# KK_Triangle_cubic.net
KiCad netlist of a schematic drawn in Altium Designer
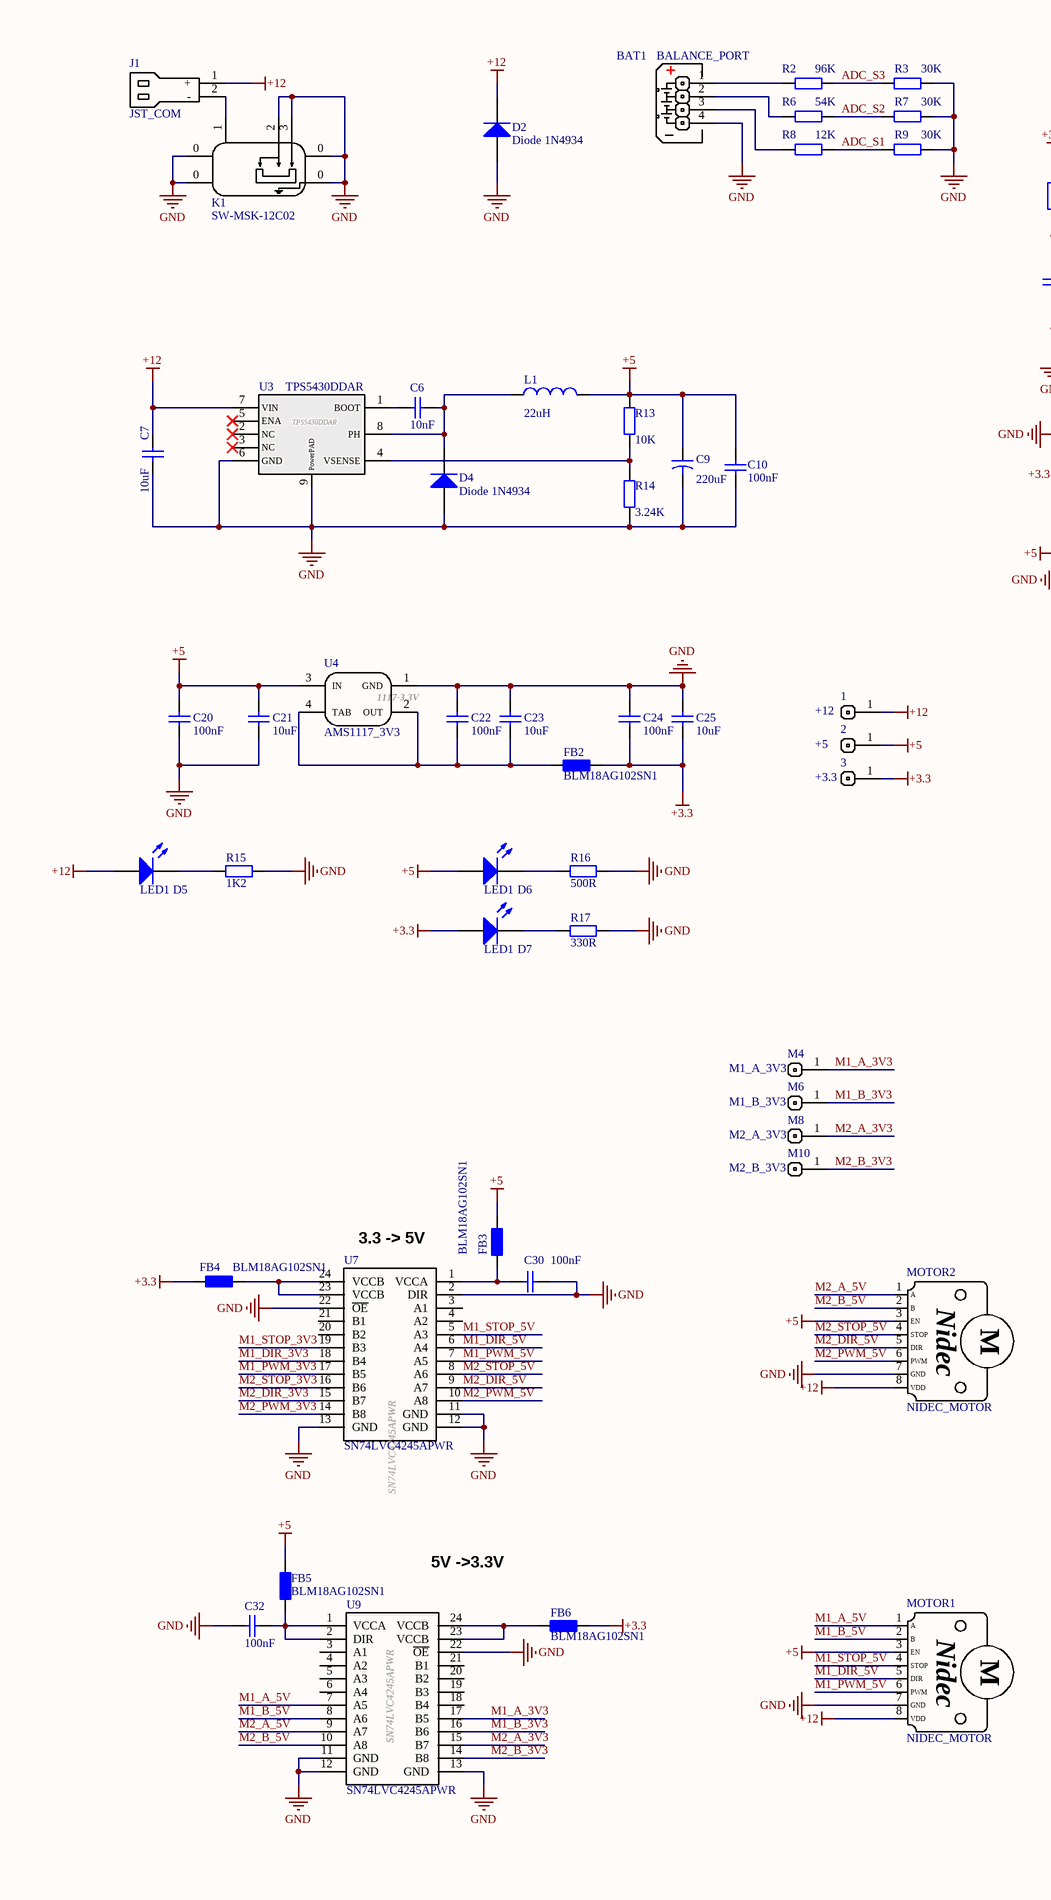
[diagram p0: KK_Triangle_cubic.SchDoc, left]
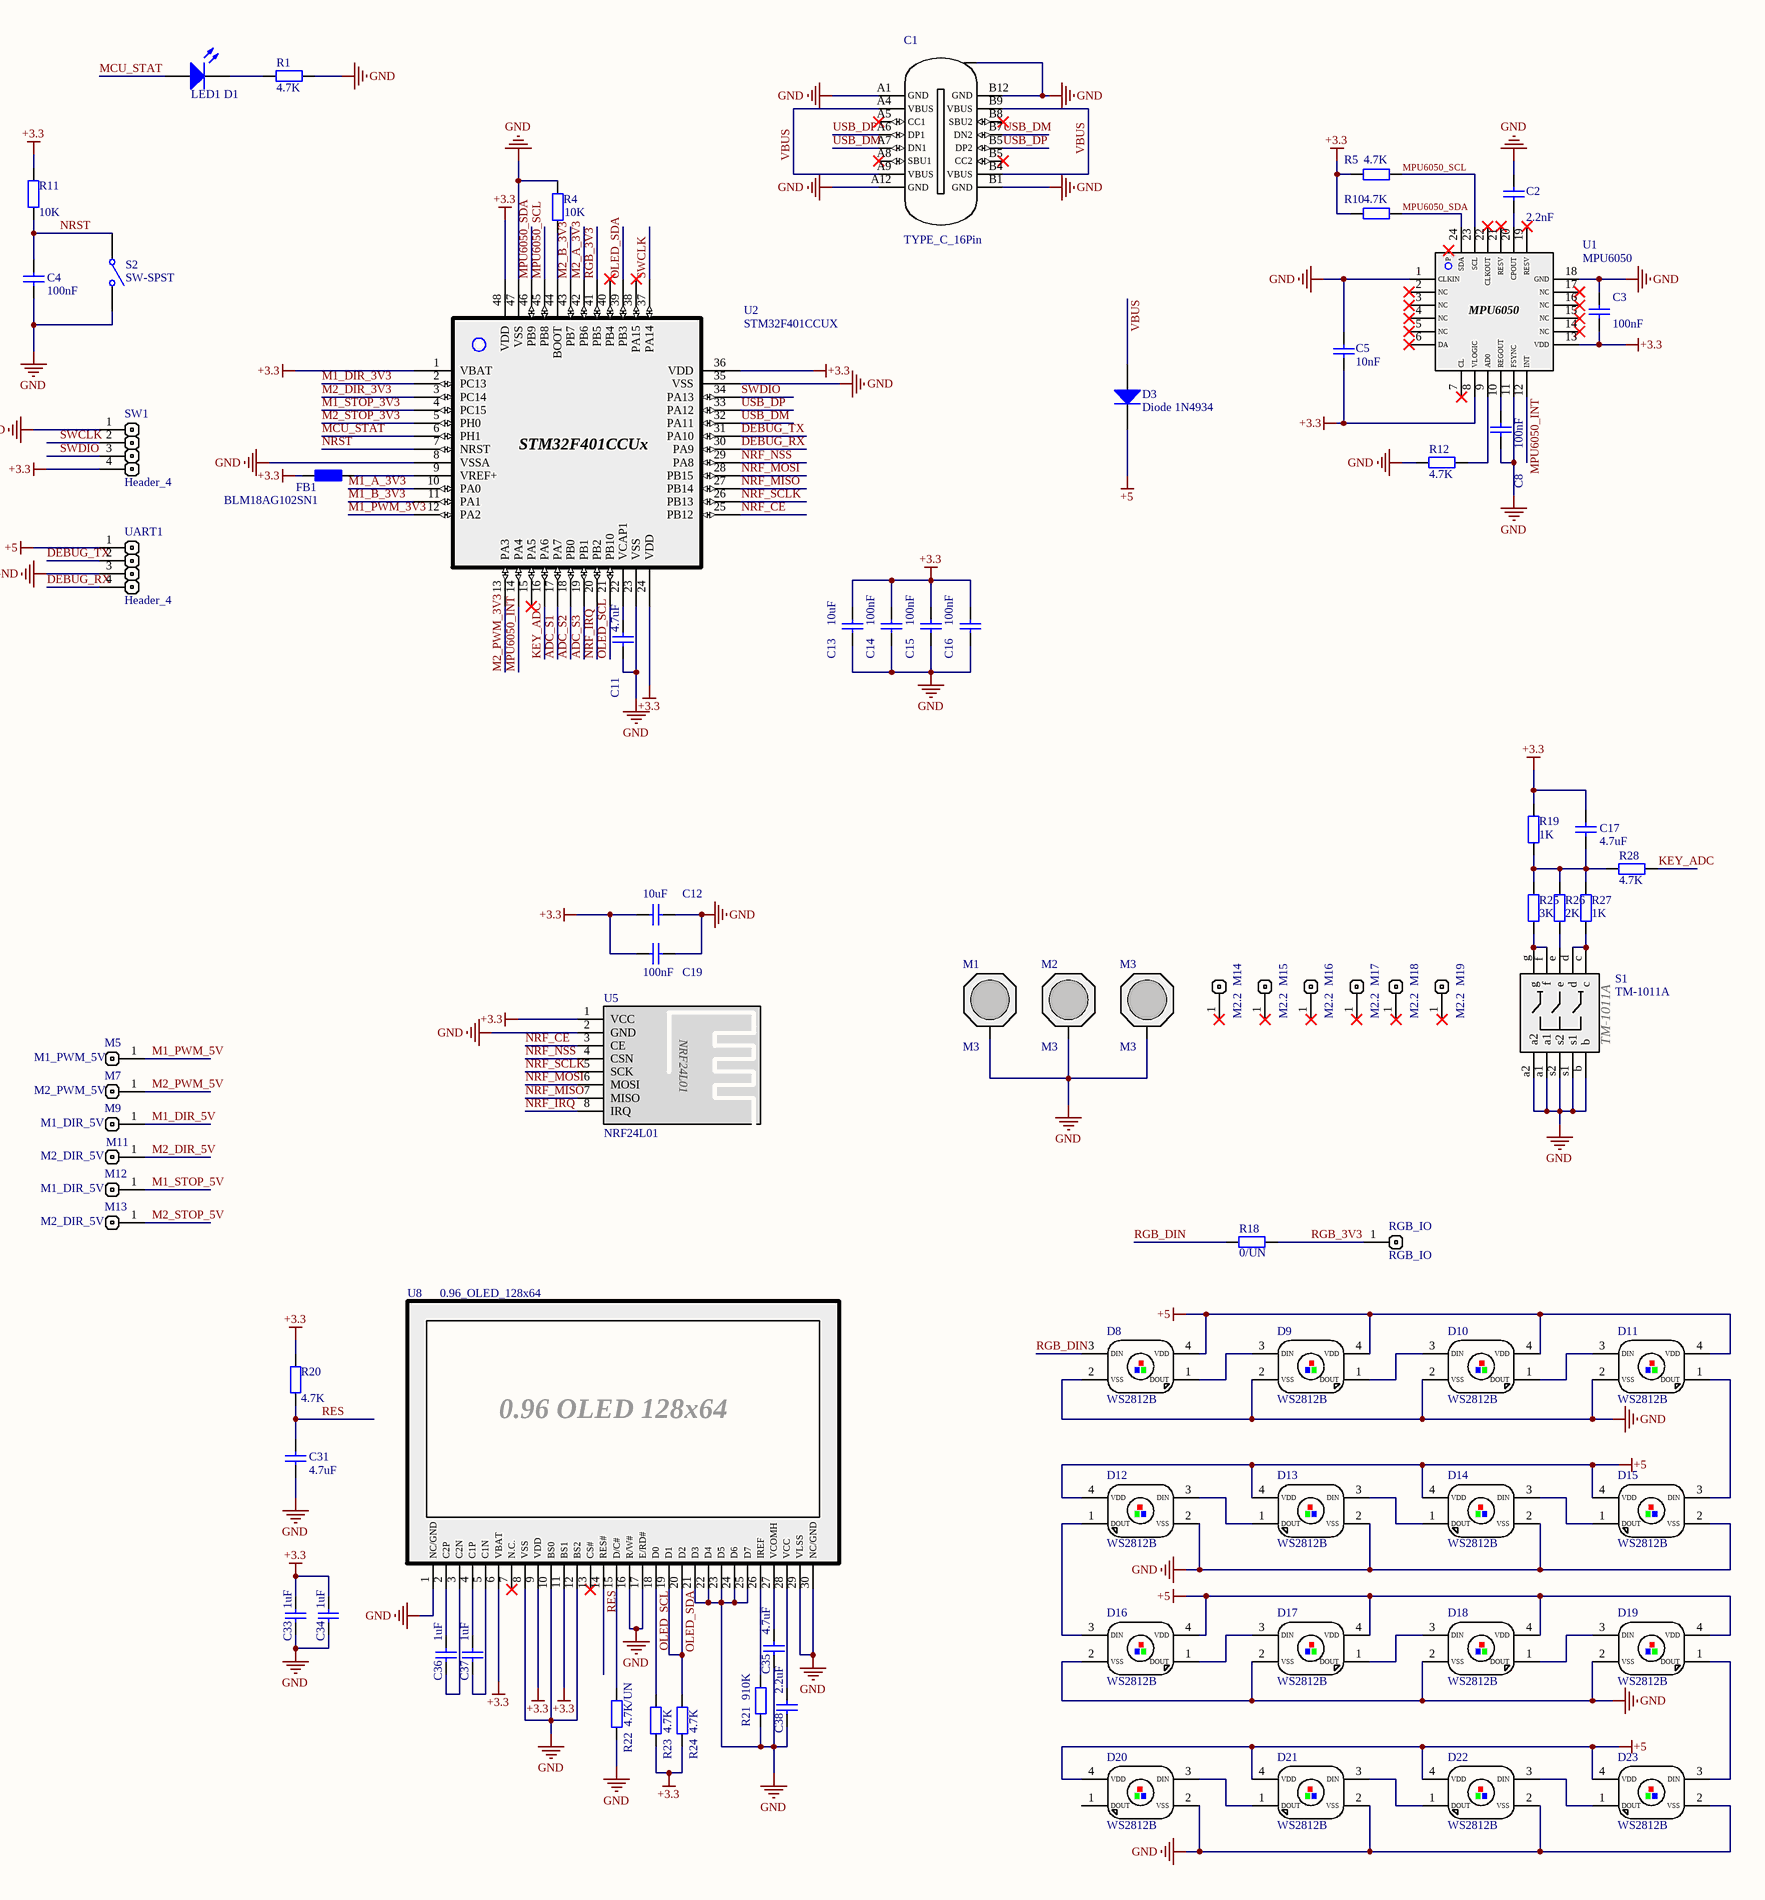
[diagram p1: KK_Triangle_cubic.SchDoc, right]

(export (version "E")
  (design (tool "Eeschema 10.0.6"))
  (components
    (comp (ref "1")
      (value "+12")
      (footprint "TEST_POINT")
      (libsource (lib "KK_Triangle_cubic") (part "TEST_POINT"))
    )
    (comp (ref "2")
      (value "+5")
      (footprint "TEST_POINT")
      (libsource (lib "KK_Triangle_cubic") (part "TEST_POINT"))
    )
    (comp (ref "3")
      (value "+3.3")
      (footprint "TEST_POINT")
      (libsource (lib "KK_Triangle_cubic") (part "TEST_POINT"))
    )
    (comp (ref "BAT1")
      (value "BALANCE_PORT")
      (footprint "XH2.54-LI-4P")
      (libsource (lib "KK_Triangle_cubic") (part "BALANCE_PORT"))
    )
    (comp (ref "C1")
      (value "TYPE_C_16Pin")
      (footprint "USB-C-SMD_TYPE-C-USB-5")
      (libsource (lib "KK_Analog") (part "TYPE_C_16Pin"))
    )
    (comp (ref "C2")
      (value "2.2nF")
      (footprint "C 0603_M")
      (description "Capacitor")
      (fields (field (name "Comment") "Cap") (field (name "PUBLISHER") "Altium Limited"))
      (libsource (lib "Miscellaneous Devices") (part "Cap"))
    )
    (comp (ref "C3")
      (value "100nF")
      (footprint "C 0603_M")
      (description "Capacitor")
      (fields (field (name "Comment") "Cap") (field (name "PUBLISHER") "Altium Limited"))
      (libsource (lib "Miscellaneous Devices") (part "Cap"))
    )
    (comp (ref "C4")
      (value "100nF")
      (footprint "C 0603_M")
      (description "Capacitor")
      (fields (field (name "Comment") "Cap") (field (name "PUBLISHER") "Altium Limited"))
      (libsource (lib "Miscellaneous Devices") (part "Cap"))
    )
    (comp (ref "C5")
      (value "10nF")
      (footprint "C 0603_M")
      (description "Capacitor")
      (fields (field (name "Comment") "Cap") (field (name "PUBLISHER") "Altium Limited"))
      (libsource (lib "Miscellaneous Devices") (part "Cap"))
    )
    (comp (ref "C6")
      (value "10nF")
      (footprint "C 0603_M")
      (description "Capacitor")
      (fields (field (name "Comment") "Cap") (field (name "PUBLISHER") "Altium Limited"))
      (libsource (lib "Miscellaneous Devices") (part "Cap"))
    )
    (comp (ref "C7")
      (value "10uF")
      (footprint "C 0603_M")
      (description "Capacitor")
      (fields (field (name "Comment") "Cap") (field (name "PUBLISHER") "Altium Limited"))
      (libsource (lib "Miscellaneous Devices") (part "Cap"))
    )
    (comp (ref "C8")
      (value "100nF")
      (footprint "C 0603_M")
      (description "Capacitor")
      (fields (field (name "Comment") "Cap") (field (name "PUBLISHER") "Altium Limited"))
      (libsource (lib "Miscellaneous Devices") (part "Cap"))
    )
    (comp (ref "C9")
      (value "220uF")
      (footprint "CM D(6.3*7.7)")
      (description "Capacitor")
      (fields (field (name "Comment") "Cap2") (field (name "PUBLISHER") "Altium Limited"))
      (libsource (lib "Miscellaneous Devices") (part "Cap2"))
    )
    (comp (ref "C10")
      (value "100nF")
      (footprint "C 0603_M")
      (description "Capacitor")
      (fields (field (name "Comment") "Cap") (field (name "PUBLISHER") "Altium Limited"))
      (libsource (lib "Miscellaneous Devices") (part "Cap"))
    )
    (comp (ref "C11")
      (value "4.7uF")
      (footprint "C 0603_M")
      (description "Capacitor")
      (fields (field (name "Comment") "Cap") (field (name "PUBLISHER") "Altium Limited"))
      (libsource (lib "Miscellaneous Devices") (part "Cap"))
    )
    (comp (ref "C12")
      (value "10uF")
      (footprint "C 0603_M")
      (description "Capacitor")
      (fields (field (name "Comment") "Cap") (field (name "PUBLISHER") "Altium Limited"))
      (libsource (lib "Miscellaneous Devices") (part "Cap"))
    )
    (comp (ref "C13")
      (value "10uF")
      (footprint "C 0603_M")
      (description "Capacitor")
      (fields (field (name "Comment") "Cap") (field (name "PUBLISHER") "Altium Limited"))
      (libsource (lib "Miscellaneous Devices") (part "Cap"))
    )
    (comp (ref "C14")
      (value "100nF")
      (footprint "C 0603_M")
      (description "Capacitor")
      (fields (field (name "Comment") "Cap") (field (name "PUBLISHER") "Altium Limited"))
      (libsource (lib "Miscellaneous Devices") (part "Cap"))
    )
    (comp (ref "C15")
      (value "100nF")
      (footprint "C 0603_M")
      (description "Capacitor")
      (fields (field (name "Comment") "Cap") (field (name "PUBLISHER") "Altium Limited"))
      (libsource (lib "Miscellaneous Devices") (part "Cap"))
    )
    (comp (ref "C16")
      (value "100nF")
      (footprint "C 0603_M")
      (description "Capacitor")
      (fields (field (name "Comment") "Cap") (field (name "PUBLISHER") "Altium Limited"))
      (libsource (lib "Miscellaneous Devices") (part "Cap"))
    )
    (comp (ref "C17")
      (value "4.7uF")
      (footprint "C 0603_M")
      (description "Capacitor")
      (fields (field (name "Comment") "Cap") (field (name "PUBLISHER") "Altium Limited"))
      (libsource (lib "Miscellaneous Devices") (part "Cap"))
    )
    (comp (ref "C19")
      (value "100nF")
      (footprint "C 0603_M")
      (description "Capacitor")
      (fields (field (name "Comment") "Cap") (field (name "PUBLISHER") "Altium Limited"))
      (libsource (lib "Miscellaneous Devices") (part "Cap"))
    )
    (comp (ref "C20")
      (value "100nF")
      (footprint "C 0603_M")
      (description "Capacitor")
      (fields (field (name "Comment") "Cap") (field (name "PUBLISHER") "Altium Limited"))
      (libsource (lib "Miscellaneous Devices") (part "Cap"))
    )
    (comp (ref "C21")
      (value "10uF")
      (footprint "C 0603_M")
      (description "Capacitor")
      (fields (field (name "Comment") "Cap") (field (name "PUBLISHER") "Altium Limited"))
      (libsource (lib "Miscellaneous Devices") (part "Cap"))
    )
    (comp (ref "C22")
      (value "100nF")
      (footprint "C 0603_M")
      (description "Capacitor")
      (fields (field (name "Comment") "Cap") (field (name "PUBLISHER") "Altium Limited"))
      (libsource (lib "Miscellaneous Devices") (part "Cap"))
    )
    (comp (ref "C23")
      (value "10uF")
      (footprint "C 0603_M")
      (description "Capacitor")
      (fields (field (name "Comment") "Cap") (field (name "PUBLISHER") "Altium Limited"))
      (libsource (lib "Miscellaneous Devices") (part "Cap"))
    )
    (comp (ref "C24")
      (value "100nF")
      (footprint "C 0603_M")
      (description "Capacitor")
      (fields (field (name "Comment") "Cap") (field (name "PUBLISHER") "Altium Limited"))
      (libsource (lib "Miscellaneous Devices") (part "Cap"))
    )
    (comp (ref "C25")
      (value "10uF")
      (footprint "C 0603_M")
      (description "Capacitor")
      (fields (field (name "Comment") "Cap") (field (name "PUBLISHER") "Altium Limited"))
      (libsource (lib "Miscellaneous Devices") (part "Cap"))
    )
    (comp (ref "C30")
      (value "100nF")
      (footprint "C 0603_M")
      (description "Capacitor")
      (fields (field (name "Comment") "Cap") (field (name "PUBLISHER") "Altium Limited"))
      (libsource (lib "Miscellaneous Devices") (part "Cap"))
    )
    (comp (ref "C31")
      (value "4.7uF")
      (footprint "C 0603_M")
      (description "Capacitor")
      (fields (field (name "Comment") "Cap") (field (name "PUBLISHER") "Altium Limited"))
      (libsource (lib "Miscellaneous Devices") (part "Cap"))
    )
    (comp (ref "C32")
      (value "100nF")
      (footprint "C 0603_M")
      (description "Capacitor")
      (fields (field (name "Comment") "Cap") (field (name "PUBLISHER") "Altium Limited"))
      (libsource (lib "Miscellaneous Devices") (part "Cap"))
    )
    (comp (ref "C33")
      (value "1uF")
      (footprint "C 0603_M")
      (description "Capacitor")
      (fields (field (name "Comment") "Cap") (field (name "PUBLISHER") "Altium Limited"))
      (libsource (lib "Miscellaneous Devices") (part "Cap"))
    )
    (comp (ref "C34")
      (value "1uF")
      (footprint "C 0603_M")
      (description "Capacitor")
      (fields (field (name "Comment") "Cap") (field (name "PUBLISHER") "Altium Limited"))
      (libsource (lib "Miscellaneous Devices") (part "Cap"))
    )
    (comp (ref "C35")
      (value "4.7uF")
      (footprint "C 0603_M")
      (description "Capacitor")
      (fields (field (name "Comment") "Cap") (field (name "PUBLISHER") "Altium Limited"))
      (libsource (lib "Miscellaneous Devices") (part "Cap"))
    )
    (comp (ref "C36")
      (value "1uF")
      (footprint "C 0603_M")
      (description "Capacitor")
      (fields (field (name "Comment") "Cap") (field (name "PUBLISHER") "Altium Limited"))
      (libsource (lib "Miscellaneous Devices") (part "Cap"))
    )
    (comp (ref "C37")
      (value "1uF")
      (footprint "C 0603_M")
      (description "Capacitor")
      (fields (field (name "Comment") "Cap") (field (name "PUBLISHER") "Altium Limited"))
      (libsource (lib "Miscellaneous Devices") (part "Cap"))
    )
    (comp (ref "C38")
      (value "2.2uF")
      (footprint "C 0603_M")
      (description "Capacitor")
      (fields (field (name "Comment") "Cap") (field (name "PUBLISHER") "Altium Limited"))
      (libsource (lib "Miscellaneous Devices") (part "Cap"))
    )
    (comp (ref "D1")
      (value "LED1")
      (footprint "LED 0805G")
      (description "Typical RED GaAs LED")
      (fields (field (name "PUBLISHER") "Altium Limited"))
      (libsource (lib "Miscellaneous Devices") (part "LED1"))
    )
    (comp (ref "D2")
      (value "Diode 1N4934")
      (footprint "1N5819(SMD)")
      (description "1 Amp Fast Recovery Rectifier")
      (fields (field (name "PUBLISHER") "Altium Limited"))
      (libsource (lib "Miscellaneous Devices") (part "Diode 1N4934"))
    )
    (comp (ref "D3")
      (value "Diode 1N4934")
      (footprint "SOD-323")
      (description "1 Amp Fast Recovery Rectifier")
      (fields (field (name "PUBLISHER") "Altium Limited"))
      (libsource (lib "Miscellaneous Devices") (part "Diode 1N4934"))
    )
    (comp (ref "D4")
      (value "Diode 1N4934")
      (footprint "1N5819(SMD)")
      (description "1 Amp Fast Recovery Rectifier")
      (fields (field (name "PUBLISHER") "Altium Limited"))
      (libsource (lib "Miscellaneous Devices") (part "Diode 1N4934"))
    )
    (comp (ref "D5")
      (value "LED1")
      (footprint "LED 0805G")
      (description "Typical RED GaAs LED")
      (fields (field (name "PUBLISHER") "Altium Limited"))
      (libsource (lib "Miscellaneous Devices") (part "LED1"))
    )
    (comp (ref "D6")
      (value "LED1")
      (footprint "LED 0805G")
      (description "Typical RED GaAs LED")
      (fields (field (name "PUBLISHER") "Altium Limited"))
      (libsource (lib "Miscellaneous Devices") (part "LED1"))
    )
    (comp (ref "D7")
      (value "LED1")
      (footprint "LED 0805G")
      (description "Typical RED GaAs LED")
      (fields (field (name "PUBLISHER") "Altium Limited"))
      (libsource (lib "Miscellaneous Devices") (part "LED1"))
    )
    (comp (ref "D8")
      (value "WS2812B")
      (footprint "WS2812B-2020")
      (libsource (lib "") (part "WS2812B_2020_1"))
    )
    (comp (ref "D9")
      (value "WS2812B")
      (footprint "WS2812B-2020")
      (libsource (lib "") (part "WS2812B_2020_1"))
    )
    (comp (ref "D10")
      (value "WS2812B")
      (footprint "WS2812B-2020")
      (libsource (lib "") (part "WS2812B_2020_1"))
    )
    (comp (ref "D11")
      (value "WS2812B")
      (footprint "WS2812B-2020")
      (libsource (lib "") (part "WS2812B_2020_1"))
    )
    (comp (ref "D12")
      (value "WS2812B")
      (footprint "WS2812B-2020")
      (libsource (lib "KK_Triangle_cubic") (part "WS2812B_2020"))
    )
    (comp (ref "D13")
      (value "WS2812B")
      (footprint "WS2812B-2020")
      (libsource (lib "KK_Triangle_cubic") (part "WS2812B_2020"))
    )
    (comp (ref "D14")
      (value "WS2812B")
      (footprint "WS2812B-2020")
      (libsource (lib "KK_Triangle_cubic") (part "WS2812B_2020"))
    )
    (comp (ref "D15")
      (value "WS2812B")
      (footprint "WS2812B-2020")
      (libsource (lib "KK_Triangle_cubic") (part "WS2812B_2020"))
    )
    (comp (ref "D16")
      (value "WS2812B")
      (footprint "WS2812B-2020")
      (libsource (lib "") (part "WS2812B_2020_1"))
    )
    (comp (ref "D17")
      (value "WS2812B")
      (footprint "WS2812B-2020")
      (libsource (lib "") (part "WS2812B_2020_1"))
    )
    (comp (ref "D18")
      (value "WS2812B")
      (footprint "WS2812B-2020")
      (libsource (lib "") (part "WS2812B_2020_1"))
    )
    (comp (ref "D19")
      (value "WS2812B")
      (footprint "WS2812B-2020")
      (libsource (lib "") (part "WS2812B_2020_1"))
    )
    (comp (ref "D20")
      (value "WS2812B")
      (footprint "WS2812B-2020")
      (libsource (lib "KK_Triangle_cubic") (part "WS2812B_2020"))
    )
    (comp (ref "D21")
      (value "WS2812B")
      (footprint "WS2812B-2020")
      (libsource (lib "KK_Triangle_cubic") (part "WS2812B_2020"))
    )
    (comp (ref "D22")
      (value "WS2812B")
      (footprint "WS2812B-2020")
      (libsource (lib "KK_Triangle_cubic") (part "WS2812B_2020"))
    )
    (comp (ref "D23")
      (value "WS2812B")
      (footprint "WS2812B-2020")
      (libsource (lib "KK_Triangle_cubic") (part "WS2812B_2020"))
    )
    (comp (ref "FB1")
      (value "BLM18AG102SN1")
      (footprint "L 0603")
      (libsource (lib "") (part "BLM18AG102SN1_2"))
    )
    (comp (ref "FB2")
      (value "BLM18AG102SN1")
      (footprint "L 0603")
      (libsource (lib "") (part "BLM18AG102SN1_2"))
    )
    (comp (ref "FB3")
      (value "BLM18AG102SN1")
      (footprint "L 0603")
      (libsource (lib "KK_Triangle_cubic") (part "BLM18AG102SN1"))
    )
    (comp (ref "FB4")
      (value "BLM18AG102SN1")
      (footprint "L 0603")
      (libsource (lib "") (part "BLM18AG102SN1_1"))
    )
    (comp (ref "FB5")
      (value "BLM18AG102SN1")
      (footprint "L 0603")
      (libsource (lib "") (part "BLM18AG102SN1_2"))
    )
    (comp (ref "FB6")
      (value "BLM18AG102SN1")
      (footprint "L 0603")
      (libsource (lib "KK_Triangle_cubic") (part "BLM18AG102SN1"))
    )
    (comp (ref "J1")
      (value "JST_COM")
      (footprint "JST_COM")
      (libsource (lib "KK_Triangle_cubic") (part "JST_COM"))
    )
    (comp (ref "K1")
      (value "SW-MSK-12C02")
      (footprint "MSK-12C01-07")
      (libsource (lib "KK_Triangle_cubic") (part "SW-MSK-12C02"))
    )
    (comp (ref "L1")
      (value "22uH")
      (footprint "CDRH74")
      (description "Inductor")
      (fields (field (name "PUBLISHER") "Altium Limited"))
      (libsource (lib "Miscellaneous Devices") (part "Inductor"))
    )
    (comp (ref "M1") (value "M3") (footprint "M3x40+6_L") (libsource (lib "KK_Triangle_cubic") (part "M3")))
    (comp (ref "M2") (value "M3") (footprint "M3x40+6_L") (libsource (lib "KK_Triangle_cubic") (part "M3")))
    (comp (ref "M3") (value "M3") (footprint "M3x40+6_L") (libsource (lib "KK_Triangle_cubic") (part "M3")))
    (comp (ref "M4")
      (value "M1_A_3V3")
      (footprint "TEST_POINT")
      (libsource (lib "KK_Triangle_cubic") (part "TEST_POINT"))
    )
    (comp (ref "M5")
      (value "M1_PWM_5V")
      (footprint "TEST_POINT")
      (libsource (lib "KK_Triangle_cubic") (part "TEST_POINT"))
    )
    (comp (ref "M6")
      (value "M1_B_3V3")
      (footprint "TEST_POINT")
      (libsource (lib "KK_Triangle_cubic") (part "TEST_POINT"))
    )
    (comp (ref "M7")
      (value "M2_PWM_5V")
      (footprint "TEST_POINT")
      (libsource (lib "KK_Triangle_cubic") (part "TEST_POINT"))
    )
    (comp (ref "M8")
      (value "M2_A_3V3")
      (footprint "TEST_POINT")
      (libsource (lib "KK_Triangle_cubic") (part "TEST_POINT"))
    )
    (comp (ref "M9")
      (value "M1_DIR_5V")
      (footprint "TEST_POINT")
      (libsource (lib "KK_Triangle_cubic") (part "TEST_POINT"))
    )
    (comp (ref "M10")
      (value "M2_B_3V3")
      (footprint "TEST_POINT")
      (libsource (lib "KK_Triangle_cubic") (part "TEST_POINT"))
    )
    (comp (ref "M11")
      (value "M2_DIR_5V")
      (footprint "TEST_POINT")
      (libsource (lib "KK_Triangle_cubic") (part "TEST_POINT"))
    )
    (comp (ref "M12")
      (value "M1_DIR_5V")
      (footprint "TEST_POINT")
      (libsource (lib "KK_Triangle_cubic") (part "TEST_POINT"))
    )
    (comp (ref "M13")
      (value "M2_DIR_5V")
      (footprint "TEST_POINT")
      (libsource (lib "KK_Triangle_cubic") (part "TEST_POINT"))
    )
    (comp (ref "M14") (value "M2.2") (footprint "H2.2") (libsource (lib "KK_Triangle_cubic") (part "M2.2")))
    (comp (ref "M15") (value "M2.2") (footprint "H2.2") (libsource (lib "KK_Triangle_cubic") (part "M2.2")))
    (comp (ref "M16") (value "M2.2") (footprint "H2.2") (libsource (lib "KK_Triangle_cubic") (part "M2.2")))
    (comp (ref "M17") (value "M2.2") (footprint "H2.2") (libsource (lib "KK_Triangle_cubic") (part "M2.2")))
    (comp (ref "M18") (value "M2.2") (footprint "H2.2") (libsource (lib "KK_Triangle_cubic") (part "M2.2")))
    (comp (ref "M19") (value "M2.2") (footprint "H2.2") (libsource (lib "KK_Triangle_cubic") (part "M2.2")))
    (comp (ref "MOTOR1")
      (value "NIDEC_MOTOR")
      (footprint "MX 1.25-LS-8P")
      (libsource (lib "KK_Triangle_cubic") (part "NIDEC_MOTOR"))
    )
    (comp (ref "MOTOR2")
      (value "NIDEC_MOTOR")
      (footprint "MX 1.25-LS-8P")
      (libsource (lib "KK_Triangle_cubic") (part "NIDEC_MOTOR"))
    )
    (comp (ref "R1")
      (value "4.7K")
      (footprint "R 0603_M")
      (description "Resistor")
      (fields (field (name "Comment") "Res2") (field (name "PUBLISHER") "Altium Limited"))
      (libsource (lib "Miscellaneous Devices") (part "Res2"))
    )
    (comp (ref "R2")
      (value "96K")
      (footprint "R 0603_M")
      (description "Resistor")
      (fields (field (name "Comment") "Res2") (field (name "PUBLISHER") "Altium Limited"))
      (libsource (lib "Miscellaneous Devices") (part "Res2"))
    )
    (comp (ref "R3")
      (value "30K")
      (footprint "R 0603_M")
      (description "Resistor")
      (fields (field (name "Comment") "Res2") (field (name "PUBLISHER") "Altium Limited"))
      (libsource (lib "Miscellaneous Devices") (part "Res2"))
    )
    (comp (ref "R4")
      (value "10K")
      (footprint "R 0603_M")
      (description "Resistor")
      (fields (field (name "Comment") "Res2") (field (name "PUBLISHER") "Altium Limited"))
      (libsource (lib "") (part "Res2_2"))
    )
    (comp (ref "R5")
      (value "4.7K")
      (footprint "R 0603_M")
      (description "Resistor")
      (fields (field (name "Comment") "Res2") (field (name "PUBLISHER") "Altium Limited"))
      (libsource (lib "Miscellaneous Devices") (part "Res2"))
    )
    (comp (ref "R6")
      (value "54K")
      (footprint "R 0603_M")
      (description "Resistor")
      (fields (field (name "Comment") "Res2") (field (name "PUBLISHER") "Altium Limited"))
      (libsource (lib "Miscellaneous Devices") (part "Res2"))
    )
    (comp (ref "R7")
      (value "30K")
      (footprint "R 0603_M")
      (description "Resistor")
      (fields (field (name "Comment") "Res2") (field (name "PUBLISHER") "Altium Limited"))
      (libsource (lib "Miscellaneous Devices") (part "Res2"))
    )
    (comp (ref "R8")
      (value "12K")
      (footprint "R 0603_M")
      (description "Resistor")
      (fields (field (name "Comment") "Res2") (field (name "PUBLISHER") "Altium Limited"))
      (libsource (lib "Miscellaneous Devices") (part "Res2"))
    )
    (comp (ref "R9")
      (value "30K")
      (footprint "R 0603_M")
      (description "Resistor")
      (fields (field (name "Comment") "Res2") (field (name "PUBLISHER") "Altium Limited"))
      (libsource (lib "Miscellaneous Devices") (part "Res2"))
    )
    (comp (ref "R10")
      (value "4.7K")
      (footprint "R 0603_M")
      (description "Resistor")
      (fields (field (name "Comment") "Res2") (field (name "PUBLISHER") "Altium Limited"))
      (libsource (lib "Miscellaneous Devices") (part "Res2"))
    )
    (comp (ref "R11")
      (value "10K")
      (footprint "R 0603_M")
      (description "Resistor")
      (fields (field (name "Comment") "Res2") (field (name "PUBLISHER") "Altium Limited"))
      (libsource (lib "") (part "Res2_2"))
    )
    (comp (ref "R12")
      (value "4.7K")
      (footprint "R 0603_M")
      (description "Resistor")
      (fields (field (name "Comment") "Res2") (field (name "PUBLISHER") "Altium Limited"))
      (libsource (lib "") (part "Res2_1"))
    )
    (comp (ref "R13")
      (value "10K")
      (footprint "R 0603_M")
      (description "Resistor")
      (fields (field (name "Comment") "Res2") (field (name "PUBLISHER") "Altium Limited"))
      (libsource (lib "") (part "Res2_2"))
    )
    (comp (ref "R14")
      (value "3.24K")
      (footprint "R 0603_M")
      (description "Resistor")
      (fields (field (name "Comment") "Res2") (field (name "PUBLISHER") "Altium Limited"))
      (libsource (lib "") (part "Res2_2"))
    )
    (comp (ref "R15")
      (value "1K2")
      (footprint "R 0603_M")
      (description "Resistor")
      (fields (field (name "Comment") "Res2") (field (name "PUBLISHER") "Altium Limited"))
      (libsource (lib "Miscellaneous Devices") (part "Res2"))
    )
    (comp (ref "R16")
      (value "500R")
      (footprint "R 0603_M")
      (description "Resistor")
      (fields (field (name "Comment") "Res2") (field (name "PUBLISHER") "Altium Limited"))
      (libsource (lib "Miscellaneous Devices") (part "Res2"))
    )
    (comp (ref "R17")
      (value "330R")
      (footprint "R 0603_M")
      (description "Resistor")
      (fields (field (name "Comment") "Res2") (field (name "PUBLISHER") "Altium Limited"))
      (libsource (lib "Miscellaneous Devices") (part "Res2"))
    )
    (comp (ref "R18")
      (value "0/UN")
      (footprint "R 0603_M")
      (description "Resistor")
      (fields (field (name "Comment") "Res2") (field (name "PUBLISHER") "Altium Limited"))
      (libsource (lib "") (part "Res2_1"))
    )
    (comp (ref "R19")
      (value "1K")
      (footprint "R 0603_M")
      (description "Resistor")
      (fields (field (name "Comment") "Res2") (field (name "PUBLISHER") "Altium Limited"))
      (libsource (lib "") (part "Res2_2"))
    )
    (comp (ref "R20")
      (value "4.7K")
      (footprint "R 0603_M")
      (description "Resistor")
      (fields (field (name "Comment") "Res2") (field (name "PUBLISHER") "Altium Limited"))
      (libsource (lib "") (part "Res2_2"))
    )
    (comp (ref "R21")
      (value "910K")
      (footprint "R 0603_M")
      (description "Resistor")
      (fields (field (name "Comment") "Res2") (field (name "PUBLISHER") "Altium Limited"))
      (libsource (lib "") (part "Res2_3"))
    )
    (comp (ref "R22")
      (value "4.7K/UN")
      (footprint "R 0603_M")
      (description "Resistor")
      (fields (field (name "Comment") "Res2") (field (name "PUBLISHER") "Altium Limited"))
      (libsource (lib "") (part "Res2_2"))
    )
    (comp (ref "R23")
      (value "4.7K")
      (footprint "R 0603_M")
      (description "Resistor")
      (fields (field (name "Comment") "Res2") (field (name "PUBLISHER") "Altium Limited"))
      (libsource (lib "") (part "Res2_2"))
    )
    (comp (ref "R24")
      (value "4.7K")
      (footprint "R 0603_M")
      (description "Resistor")
      (fields (field (name "Comment") "Res2") (field (name "PUBLISHER") "Altium Limited"))
      (libsource (lib "") (part "Res2_2"))
    )
    (comp (ref "R25")
      (value "3K")
      (footprint "R 0603_M")
      (description "Resistor")
      (fields (field (name "Comment") "Res2") (field (name "PUBLISHER") "Altium Limited"))
      (libsource (lib "") (part "Res2_3"))
    )
    (comp (ref "R26")
      (value "2K")
      (footprint "R 0603_M")
      (description "Resistor")
      (fields (field (name "Comment") "Res2") (field (name "PUBLISHER") "Altium Limited"))
      (libsource (lib "") (part "Res2_3"))
    )
    (comp (ref "R27")
      (value "1K")
      (footprint "R 0603_M")
      (description "Resistor")
      (fields (field (name "Comment") "Res2") (field (name "PUBLISHER") "Altium Limited"))
      (libsource (lib "") (part "Res2_3"))
    )
    (comp (ref "R28")
      (value "4.7K")
      (footprint "R 0603_M")
      (description "Resistor")
      (fields (field (name "Comment") "Res2") (field (name "PUBLISHER") "Altium Limited"))
      (libsource (lib "Miscellaneous Devices") (part "Res2"))
    )
    (comp (ref "RGB_IO")
      (value "RGB_IO")
      (footprint "TEST_POINT")
      (libsource (lib "KK_Triangle_cubic") (part "TEST_POINT"))
    )
    (comp (ref "S1")
      (value "TM-1011A")
      (footprint "TM-1011A")
      (libsource (lib "KK_Triangle_cubic") (part "TM-1011A"))
    )
    (comp (ref "S2")
      (value "SW-SPST")
      (footprint "TSW SMD-3*6*2.5")
      (description "Single-Pole, Single-Throw Switch")
      (fields (field (name "PUBLISHER") "Altium Limited"))
      (libsource (lib "Miscellaneous Devices") (part "SW-SPST"))
    )
    (comp (ref "SW1")
      (value "Header_4")
      (footprint "PH2.0-L-Z-4P")
      (libsource (lib "KK_Triangle_cubic") (part "Header_4"))
    )
    (comp (ref "U1")
      (value "MPU6050")
      (footprint "QFN24 4x4_M")
      (libsource (lib "KK_Triangle_cubic") (part "MPU6050"))
    )
    (comp (ref "U2")
      (value "STM32F401CCUX")
      (footprint "STM-UFQFPN48_M")
      (libsource (lib "KK_Triangle_cubic") (part "STM32F401CCUX"))
    )
    (comp (ref "U3")
      (value "TPS5430DDAR")
      (footprint "TPS5430DDAR")
      (libsource (lib "KK_Triangle_cubic") (part "TPS5430DDAR"))
    )
    (comp (ref "U4")
      (value "AMS1117_3V3")
      (footprint "SOT223_M")
      (libsource (lib "altium-import") (part "root_0_mirrored_AMS1117_3V3_"))
    )
    (comp (ref "U5")
      (value "NRF24L01")
      (footprint "NRF24L01_MIN")
      (libsource (lib "KK_Triangle_cubic") (part "NRF24L01"))
    )
    (comp (ref "U7")
      (value "SN74LVC4245APWR")
      (footprint "TSSOP24_M")
      (libsource (lib "") (part "SN74LVC4245APWR_1"))
    )
    (comp (ref "U8")
      (value "0.96_OLED_128x64")
      (footprint "0.96_OLED")
      (libsource (lib "KK_Triangle_cubic") (part "0.96_OLED_128x64"))
    )
    (comp (ref "U9")
      (value "SN74LVC4245APWR")
      (footprint "TSSOP24_M")
      (libsource (lib "KK_Triangle_cubic") (part "SN74LVC4245APWR"))
    )
    (comp (ref "UART1")
      (value "Header_4")
      (footprint "PH2.0-L-Z-4P")
      (libsource (lib "KK_Triangle_cubic") (part "Header_4"))
    )
  )
  (nets
    (net (code "1") (name "+3.3") (class "Default")
      (node (ref "3") (pin "1") (pinfunction "1_1") (pintype "power_in"))
      (node (ref "C12") (pin "2") (pinfunction "2_2") (pintype "passive"))
      (node (ref "C13") (pin "2") (pinfunction "2_2") (pintype "passive"))
      (node (ref "C14") (pin "2") (pinfunction "2_2") (pintype "passive"))
      (node (ref "C15") (pin "2") (pinfunction "2_2") (pintype "passive"))
      (node (ref "C16") (pin "2") (pinfunction "2_2") (pintype "passive"))
      (node (ref "C17") (pin "1") (pinfunction "1_1") (pintype "passive"))
      (node (ref "C19") (pin "2") (pinfunction "2_2") (pintype "passive"))
      (node (ref "C24") (pin "1") (pinfunction "1_1") (pintype "passive"))
      (node (ref "C25") (pin "1") (pinfunction "1_1") (pintype "passive"))
      (node (ref "C3") (pin "1") (pinfunction "1_1") (pintype "passive"))
      (node (ref "C33") (pin "2") (pinfunction "2_2") (pintype "passive"))
      (node (ref "C34") (pin "2") (pinfunction "2_2") (pintype "passive"))
      (node (ref "C5") (pin "1") (pinfunction "1_1") (pintype "passive"))
      (node (ref "D7") (pin "1") (pinfunction "A_1") (pintype "passive"))
      (node (ref "FB1") (pin "1") (pinfunction "1_1") (pintype "passive"))
      (node (ref "FB2") (pin "2") (pinfunction "2_2") (pintype "passive"))
      (node (ref "FB4") (pin "2") (pinfunction "2_2") (pintype "passive"))
      (node (ref "FB6") (pin "2") (pinfunction "2_2") (pintype "passive"))
      (node (ref "R10") (pin "2") (pinfunction "2_2") (pintype "passive"))
      (node (ref "R11") (pin "2") (pinfunction "2_2") (pintype "passive"))
      (node (ref "R19") (pin "2") (pinfunction "2_2") (pintype "passive"))
      (node (ref "R20") (pin "2") (pinfunction "2_2") (pintype "passive"))
      (node (ref "R23") (pin "1") (pinfunction "1_1") (pintype "passive"))
      (node (ref "R24") (pin "1") (pinfunction "1_1") (pintype "passive"))
      (node (ref "R5") (pin "2") (pinfunction "2_2") (pintype "passive"))
      (node (ref "SW1") (pin "4") (pinfunction "4_4") (pintype "power_in"))
      (node (ref "U1") (pin "13") (pinfunction "VDD_13") (pintype "power_in"))
      (node (ref "U1") (pin "8") (pinfunction "VLOGIC_8") (pintype "power_in"))
      (node (ref "U2") (pin "1") (pinfunction "VBAT_1") (pintype "power_in"))
      (node (ref "U2") (pin "24") (pinfunction "VDD_24") (pintype "power_in"))
      (node (ref "U2") (pin "36") (pinfunction "VDD_36") (pintype "power_in"))
      (node (ref "U2") (pin "48") (pinfunction "VDD_48") (pintype "power_in"))
      (node (ref "U5") (pin "1") (pinfunction "VCC_1") (pintype "power_in"))
      (node (ref "U8") (pin "11") (pinfunction "BS1_11") (pintype "power_in"))
      (node (ref "U8") (pin "6") (pinfunction "VBAT_6") (pintype "power_in"))
      (node (ref "U8") (pin "9") (pinfunction "VDD_9") (pintype "power_in"))
    )
    (net (code "2") (name "+5") (class "Default")
      (node (ref "2") (pin "1") (pinfunction "1_1") (pintype "power_in"))
      (node (ref "C10") (pin "1") (pinfunction "1_1") (pintype "passive"))
      (node (ref "C20") (pin "2") (pinfunction "2_2") (pintype "passive"))
      (node (ref "C21") (pin "2") (pinfunction "2_2") (pintype "passive"))
      (node (ref "C9") (pin "1") (pinfunction "1_1") (pintype "passive"))
      (node (ref "D10") (pin "4") (pinfunction "VDD_4") (pintype "power_in"))
      (node (ref "D11") (pin "4") (pinfunction "VDD_4") (pintype "power_in"))
      (node (ref "D12") (pin "4") (pinfunction "VDD_4") (pintype "power_in"))
      (node (ref "D13") (pin "4") (pinfunction "VDD_4") (pintype "power_in"))
      (node (ref "D14") (pin "4") (pinfunction "VDD_4") (pintype "power_in"))
      (node (ref "D15") (pin "4") (pinfunction "VDD_4") (pintype "power_in"))
      (node (ref "D16") (pin "4") (pinfunction "VDD_4") (pintype "power_in"))
      (node (ref "D17") (pin "4") (pinfunction "VDD_4") (pintype "power_in"))
      (node (ref "D18") (pin "4") (pinfunction "VDD_4") (pintype "power_in"))
      (node (ref "D19") (pin "4") (pinfunction "VDD_4") (pintype "power_in"))
      (node (ref "D20") (pin "4") (pinfunction "VDD_4") (pintype "power_in"))
      (node (ref "D21") (pin "4") (pinfunction "VDD_4") (pintype "power_in"))
      (node (ref "D22") (pin "4") (pinfunction "VDD_4") (pintype "power_in"))
      (node (ref "D23") (pin "4") (pinfunction "VDD_4") (pintype "power_in"))
      (node (ref "D3") (pin "K") (pinfunction "K_K") (pintype "passive"))
      (node (ref "D6") (pin "1") (pinfunction "A_1") (pintype "passive"))
      (node (ref "D8") (pin "4") (pinfunction "VDD_4") (pintype "power_in"))
      (node (ref "D9") (pin "4") (pinfunction "VDD_4") (pintype "power_in"))
      (node (ref "FB3") (pin "2") (pinfunction "2_2") (pintype "passive"))
      (node (ref "FB5") (pin "2") (pinfunction "2_2") (pintype "passive"))
      (node (ref "L1") (pin "2") (pinfunction "2_2") (pintype "passive"))
      (node (ref "MOTOR1") (pin "3") (pinfunction "EN_3") (pintype "power_in"))
      (node (ref "MOTOR2") (pin "3") (pinfunction "EN_3") (pintype "power_in"))
      (node (ref "R13") (pin "2") (pinfunction "2_2") (pintype "passive"))
      (node (ref "U4") (pin "3") (pinfunction "IN_3") (pintype "power_in"))
      (node (ref "UART1") (pin "1") (pinfunction "1_1") (pintype "power_in"))
    )
    (net (code "3") (name "+12") (class "Default")
      (node (ref "1") (pin "1") (pinfunction "1_1") (pintype "power_in"))
      (node (ref "C7") (pin "2") (pinfunction "2_2") (pintype "passive"))
      (node (ref "D2") (pin "K") (pinfunction "K_K") (pintype "passive"))
      (node (ref "D5") (pin "1") (pinfunction "A_1") (pintype "passive"))
      (node (ref "J1") (pin "1") (pinfunction "+_1") (pintype "power_in"))
      (node (ref "MOTOR1") (pin "8") (pinfunction "VDD_8") (pintype "power_in"))
      (node (ref "MOTOR2") (pin "8") (pinfunction "VDD_8") (pintype "power_in"))
      (node (ref "U3") (pin "7") (pinfunction "VIN_7") (pintype "power_in"))
    )
    (net (code "4") (name "/ADC_S1") (class "Default")
      (node (ref "R8") (pin "1") (pinfunction "1_1") (pintype "passive"))
      (node (ref "R9") (pin "2") (pinfunction "2_2") (pintype "passive"))
      (node (ref "U2") (pin "17") (pinfunction "PA7_17") (pintype "bidirectional"))
    )
    (net (code "5") (name "/ADC_S2") (class "Default")
      (node (ref "R6") (pin "1") (pinfunction "1_1") (pintype "passive"))
      (node (ref "R7") (pin "2") (pinfunction "2_2") (pintype "passive"))
      (node (ref "U2") (pin "18") (pinfunction "PB0_18") (pintype "bidirectional"))
    )
    (net (code "6") (name "/ADC_S3") (class "Default")
      (node (ref "R2") (pin "1") (pinfunction "1_1") (pintype "passive"))
      (node (ref "R3") (pin "2") (pinfunction "2_2") (pintype "passive"))
      (node (ref "U2") (pin "19") (pinfunction "PB1_19") (pintype "bidirectional"))
    )
    (net (code "7") (name "/DEBUG_RX") (class "Default")
      (node (ref "U2") (pin "30") (pinfunction "PA9_30") (pintype "bidirectional"))
      (node (ref "UART1") (pin "4") (pinfunction "4_4") (pintype "power_in"))
    )
    (net (code "8") (name "/DEBUG_TX") (class "Default")
      (node (ref "U2") (pin "31") (pinfunction "PA10_31") (pintype "bidirectional"))
      (node (ref "UART1") (pin "2") (pinfunction "2_2") (pintype "power_in"))
    )
    (net (code "9") (name "/KEY_ADC") (class "Default")
      (node (ref "R28") (pin "1") (pinfunction "1_1") (pintype "passive"))
      (node (ref "U2") (pin "16") (pinfunction "PA6_16") (pintype "bidirectional"))
    )
    (net (code "10") (name "/M1_A_3V3") (class "Default")
      (node (ref "M4") (pin "1") (pinfunction "1_1") (pintype "power_in"))
      (node (ref "U2") (pin "10") (pinfunction "PA0_10") (pintype "bidirectional"))
      (node (ref "U9") (pin "17") (pinfunction "B5_17") (pintype "power_in"))
    )
    (net (code "11") (name "/M1_A_5V") (class "Default")
      (node (ref "MOTOR1") (pin "1") (pinfunction "A_1") (pintype "power_in"))
      (node (ref "U9") (pin "7") (pinfunction "A5_7") (pintype "power_in"))
    )
    (net (code "12") (name "/M1_B_3V3") (class "Default")
      (node (ref "M6") (pin "1") (pinfunction "1_1") (pintype "power_in"))
      (node (ref "U2") (pin "11") (pinfunction "PA1_11") (pintype "bidirectional"))
      (node (ref "U9") (pin "16") (pinfunction "B6_16") (pintype "power_in"))
    )
    (net (code "13") (name "/M1_B_5V") (class "Default")
      (node (ref "MOTOR1") (pin "2") (pinfunction "B_2") (pintype "power_in"))
      (node (ref "U9") (pin "8") (pinfunction "A6_8") (pintype "power_in"))
    )
    (net (code "14") (name "/M1_DIR_3V3") (class "Default")
      (node (ref "U2") (pin "2") (pinfunction "PC13_2") (pintype "bidirectional"))
      (node (ref "U7") (pin "18") (pinfunction "B4_18") (pintype "power_in"))
    )
    (net (code "15") (name "/M1_DIR_5V") (class "Default")
      (node (ref "M9") (pin "1") (pinfunction "1_1") (pintype "power_in"))
      (node (ref "MOTOR1") (pin "5") (pinfunction "DIR_5") (pintype "power_in"))
      (node (ref "U7") (pin "6") (pinfunction "A4_6") (pintype "power_in"))
    )
    (net (code "16") (name "/M1_PWM_3V3") (class "Default")
      (node (ref "U2") (pin "12") (pinfunction "PA2_12") (pintype "bidirectional"))
      (node (ref "U7") (pin "17") (pinfunction "B5_17") (pintype "power_in"))
    )
    (net (code "17") (name "/M1_PWM_5V") (class "Default")
      (node (ref "M5") (pin "1") (pinfunction "1_1") (pintype "power_in"))
      (node (ref "MOTOR1") (pin "6") (pinfunction "PWM_6") (pintype "power_in"))
      (node (ref "U7") (pin "7") (pinfunction "A5_7") (pintype "power_in"))
    )
    (net (code "18") (name "/M1_STOP_3V3") (class "Default")
      (node (ref "U2") (pin "4") (pinfunction "PC15_4") (pintype "bidirectional"))
      (node (ref "U7") (pin "19") (pinfunction "B3_19") (pintype "power_in"))
    )
    (net (code "19") (name "/M1_STOP_5V") (class "Default")
      (node (ref "M12") (pin "1") (pinfunction "1_1") (pintype "power_in"))
      (node (ref "MOTOR1") (pin "4") (pinfunction "STOP_4") (pintype "power_in"))
      (node (ref "U7") (pin "5") (pinfunction "A3_5") (pintype "power_in"))
    )
    (net (code "20") (name "/M2_A_3V3") (class "Default")
      (node (ref "M8") (pin "1") (pinfunction "1_1") (pintype "power_in"))
      (node (ref "U2") (pin "42") (pinfunction "PB6_42") (pintype "bidirectional"))
      (node (ref "U9") (pin "15") (pinfunction "B7_15") (pintype "power_in"))
    )
    (net (code "21") (name "/M2_A_5V") (class "Default")
      (node (ref "MOTOR2") (pin "1") (pinfunction "A_1") (pintype "power_in"))
      (node (ref "U9") (pin "9") (pinfunction "A7_9") (pintype "power_in"))
    )
    (net (code "22") (name "/M2_B_3V3") (class "Default")
      (node (ref "M10") (pin "1") (pinfunction "1_1") (pintype "power_in"))
      (node (ref "U2") (pin "43") (pinfunction "PB7_43") (pintype "bidirectional"))
      (node (ref "U9") (pin "14") (pinfunction "B8_14") (pintype "power_in"))
    )
    (net (code "23") (name "/M2_B_5V") (class "Default")
      (node (ref "MOTOR2") (pin "2") (pinfunction "B_2") (pintype "power_in"))
      (node (ref "U9") (pin "10") (pinfunction "A8_10") (pintype "power_in"))
    )
    (net (code "24") (name "/M2_DIR_3V3") (class "Default")
      (node (ref "U2") (pin "3") (pinfunction "PC14_3") (pintype "bidirectional"))
      (node (ref "U7") (pin "15") (pinfunction "B7_15") (pintype "power_in"))
    )
    (net (code "25") (name "/M2_DIR_5V") (class "Default")
      (node (ref "M11") (pin "1") (pinfunction "1_1") (pintype "power_in"))
      (node (ref "MOTOR2") (pin "5") (pinfunction "DIR_5") (pintype "power_in"))
      (node (ref "U7") (pin "9") (pinfunction "A7_9") (pintype "power_in"))
    )
    (net (code "26") (name "/M2_PWM_3V3") (class "Default")
      (node (ref "U2") (pin "13") (pinfunction "PA3_13") (pintype "bidirectional"))
      (node (ref "U7") (pin "14") (pinfunction "B8_14") (pintype "power_in"))
    )
    (net (code "27") (name "/M2_PWM_5V") (class "Default")
      (node (ref "M7") (pin "1") (pinfunction "1_1") (pintype "power_in"))
      (node (ref "MOTOR2") (pin "6") (pinfunction "PWM_6") (pintype "power_in"))
      (node (ref "U7") (pin "10") (pinfunction "A8_10") (pintype "power_in"))
    )
    (net (code "28") (name "/M2_STOP_3V3") (class "Default")
      (node (ref "U2") (pin "5") (pinfunction "PH0_5") (pintype "bidirectional"))
      (node (ref "U7") (pin "16") (pinfunction "B6_16") (pintype "power_in"))
    )
    (net (code "29") (name "/M2_STOP_5V") (class "Default")
      (node (ref "M13") (pin "1") (pinfunction "1_1") (pintype "power_in"))
      (node (ref "MOTOR2") (pin "4") (pinfunction "STOP_4") (pintype "power_in"))
      (node (ref "U7") (pin "8") (pinfunction "A6_8") (pintype "power_in"))
    )
    (net (code "30") (name "/MCU_STAT") (class "Default")
      (node (ref "D1") (pin "1") (pinfunction "A_1") (pintype "passive"))
      (node (ref "U2") (pin "6") (pinfunction "PH1_6") (pintype "bidirectional"))
    )
    (net (code "31") (name "/MPU6050_INT") (class "Default")
      (node (ref "U1") (pin "12") (pinfunction "INT_12") (pintype "power_in"))
      (node (ref "U2") (pin "14") (pinfunction "PA4_14") (pintype "bidirectional"))
    )
    (net (code "32") (name "/MPU6050_SCL") (class "Default")
      (node (ref "R5") (pin "1") (pinfunction "1_1") (pintype "passive"))
      (node (ref "U1") (pin "23") (pinfunction "SCL_23") (pintype "power_in"))
      (node (ref "U2") (pin "45") (pinfunction "PB8_45") (pintype "bidirectional"))
    )
    (net (code "33") (name "/MPU6050_SDA") (class "Default")
      (node (ref "R10") (pin "1") (pinfunction "1_1") (pintype "passive"))
      (node (ref "U1") (pin "24") (pinfunction "SDA_24") (pintype "power_in"))
      (node (ref "U2") (pin "46") (pinfunction "PB9_46") (pintype "bidirectional"))
    )
    (net (code "34") (name "/NRF_CE") (class "Default")
      (node (ref "U2") (pin "25") (pinfunction "PB12_25") (pintype "bidirectional"))
      (node (ref "U5") (pin "3") (pinfunction "CE_3") (pintype "power_in"))
    )
    (net (code "35") (name "/NRF_IRQ") (class "Default")
      (node (ref "U2") (pin "20") (pinfunction "PB2_20") (pintype "bidirectional"))
      (node (ref "U5") (pin "8") (pinfunction "IRQ_8") (pintype "power_in"))
    )
    (net (code "36") (name "/NRF_MISO") (class "Default")
      (node (ref "U2") (pin "27") (pinfunction "PB14_27") (pintype "bidirectional"))
      (node (ref "U5") (pin "7") (pinfunction "MISO_7") (pintype "power_in"))
    )
    (net (code "37") (name "/NRF_MOSI") (class "Default")
      (node (ref "U2") (pin "28") (pinfunction "PB15_28") (pintype "bidirectional"))
      (node (ref "U5") (pin "6") (pinfunction "MOSI_6") (pintype "power_in"))
    )
    (net (code "38") (name "/NRF_NSS") (class "Default")
      (node (ref "U2") (pin "29") (pinfunction "PA8_29") (pintype "bidirectional"))
      (node (ref "U5") (pin "4") (pinfunction "CSN_4") (pintype "power_in"))
    )
    (net (code "39") (name "/NRF_SCLK") (class "Default")
      (node (ref "U2") (pin "26") (pinfunction "PB13_26") (pintype "bidirectional"))
      (node (ref "U5") (pin "5") (pinfunction "SCK_5") (pintype "power_in"))
    )
    (net (code "40") (name "/NRST") (class "Default")
      (node (ref "C4") (pin "2") (pinfunction "2_2") (pintype "passive"))
      (node (ref "R11") (pin "1") (pinfunction "1_1") (pintype "passive"))
      (node (ref "S2") (pin "1") (pinfunction "COMMON_1") (pintype "passive"))
      (node (ref "U2") (pin "7") (pinfunction "NRST_7") (pintype "bidirectional"))
    )
    (net (code "41") (name "/OLED_SCL") (class "Default")
      (node (ref "R23") (pin "2") (pinfunction "2_2") (pintype "passive"))
      (node (ref "U2") (pin "21") (pinfunction "PB10_21") (pintype "bidirectional"))
      (node (ref "U8") (pin "18") (pinfunction "D0_18") (pintype "power_in"))
    )
    (net (code "42") (name "/OLED_SDA") (class "Default")
      (node (ref "R24") (pin "2") (pinfunction "2_2") (pintype "passive"))
      (node (ref "U2") (pin "39") (pinfunction "PB3_39") (pintype "bidirectional"))
      (node (ref "U8") (pin "19") (pinfunction "D1_19") (pintype "power_in"))
      (node (ref "U8") (pin "20") (pinfunction "D2_20") (pintype "power_in"))
    )
    (net (code "43") (name "/RES") (class "Default")
      (node (ref "C31") (pin "2") (pinfunction "2_2") (pintype "passive"))
      (node (ref "R20") (pin "1") (pinfunction "1_1") (pintype "passive"))
      (node (ref "U8") (pin "14") (pinfunction "RES#_14") (pintype "power_in"))
    )
    (net (code "44") (name "/RGB_3V3") (class "Default")
      (node (ref "R18") (pin "2") (pinfunction "2_2") (pintype "passive"))
      (node (ref "RGB_IO") (pin "1") (pinfunction "1_1") (pintype "power_in"))
      (node (ref "U2") (pin "41") (pinfunction "PB5_41") (pintype "bidirectional"))
    )
    (net (code "45") (name "/RGB_DIN") (class "Default")
      (node (ref "D8") (pin "3") (pinfunction "DIN_3") (pintype "power_in"))
      (node (ref "R18") (pin "1") (pinfunction "1_1") (pintype "passive"))
    )
    (net (code "46") (name "/SWCLK") (class "Default")
      (node (ref "SW1") (pin "2") (pinfunction "2_2") (pintype "power_in"))
      (node (ref "U2") (pin "37") (pinfunction "PA14_37") (pintype "bidirectional"))
    )
    (net (code "47") (name "/SWDIO") (class "Default")
      (node (ref "SW1") (pin "3") (pinfunction "3_3") (pintype "power_in"))
      (node (ref "U2") (pin "34") (pinfunction "PA13_34") (pintype "bidirectional"))
    )
    (net (code "48") (name "/USB_DM") (class "Default")
      (node (ref "C1") (pin "A7") (pinfunction "DN1_A7") (pintype "bidirectional"))
      (node (ref "C1") (pin "B7") (pinfunction "DN2_B7") (pintype "bidirectional"))
      (node (ref "U2") (pin "32") (pinfunction "PA11_32") (pintype "bidirectional"))
    )
    (net (code "49") (name "/USB_DP") (class "Default")
      (node (ref "C1") (pin "A6") (pinfunction "DP1_A6") (pintype "bidirectional"))
      (node (ref "C1") (pin "B5") (pinfunction "DP2_B5") (pintype "bidirectional"))
      (node (ref "U2") (pin "33") (pinfunction "PA12_33") (pintype "bidirectional"))
    )
    (net (code "50") (name "/VBUS") (class "Default")
      (node (ref "C1") (pin "A4") (pinfunction "VBUS_A4") (pintype "power_in"))
      (node (ref "C1") (pin "A9") (pinfunction "VBUS_A9") (pintype "power_in"))
      (node (ref "C1") (pin "B4") (pinfunction "VBUS_B4") (pintype "power_in"))
      (node (ref "C1") (pin "B9") (pinfunction "VBUS_B9") (pintype "power_in"))
      (node (ref "D3") (pin "A") (pinfunction "A_A") (pintype "passive"))
    )
    (net (code "51") (name "GND") (class "Default")
      (node (ref "BAT1") (pin "4") (pinfunction "4_4") (pintype "power_in"))
      (node (ref "C1") (pin "0") (pinfunction "0_0") (pintype "power_in"))
      (node (ref "C1") (pin "A1") (pinfunction "GND_A1") (pintype "power_in"))
      (node (ref "C1") (pin "A12") (pinfunction "GND_A12") (pintype "power_in"))
      (node (ref "C1") (pin "B1") (pinfunction "GND_B1") (pintype "power_in"))
      (node (ref "C1") (pin "B12") (pinfunction "GND_B12") (pintype "power_in"))
      (node (ref "C10") (pin "2") (pinfunction "2_2") (pintype "passive"))
      (node (ref "C11") (pin "2") (pinfunction "2_2") (pintype "passive"))
      (node (ref "C12") (pin "1") (pinfunction "1_1") (pintype "passive"))
      (node (ref "C13") (pin "1") (pinfunction "1_1") (pintype "passive"))
      (node (ref "C14") (pin "1") (pinfunction "1_1") (pintype "passive"))
      (node (ref "C15") (pin "1") (pinfunction "1_1") (pintype "passive"))
      (node (ref "C16") (pin "1") (pinfunction "1_1") (pintype "passive"))
      (node (ref "C19") (pin "1") (pinfunction "1_1") (pintype "passive"))
      (node (ref "C2") (pin "2") (pinfunction "2_2") (pintype "passive"))
      (node (ref "C20") (pin "1") (pinfunction "1_1") (pintype "passive"))
      (node (ref "C21") (pin "1") (pinfunction "1_1") (pintype "passive"))
      (node (ref "C22") (pin "2") (pinfunction "2_2") (pintype "passive"))
      (node (ref "C23") (pin "2") (pinfunction "2_2") (pintype "passive"))
      (node (ref "C24") (pin "2") (pinfunction "2_2") (pintype "passive"))
      (node (ref "C25") (pin "2") (pinfunction "2_2") (pintype "passive"))
      (node (ref "C3") (pin "2") (pinfunction "2_2") (pintype "passive"))
      (node (ref "C30") (pin "1") (pinfunction "1_1") (pintype "passive"))
      (node (ref "C31") (pin "1") (pinfunction "1_1") (pintype "passive"))
      (node (ref "C32") (pin "1") (pinfunction "1_1") (pintype "passive"))
      (node (ref "C33") (pin "1") (pinfunction "1_1") (pintype "passive"))
      (node (ref "C34") (pin "1") (pinfunction "1_1") (pintype "passive"))
      (node (ref "C35") (pin "2") (pinfunction "2_2") (pintype "passive"))
      (node (ref "C38") (pin "2") (pinfunction "2_2") (pintype "passive"))
      (node (ref "C4") (pin "1") (pinfunction "1_1") (pintype "passive"))
      (node (ref "C5") (pin "2") (pinfunction "2_2") (pintype "passive"))
      (node (ref "C7") (pin "1") (pinfunction "1_1") (pintype "passive"))
      (node (ref "C8") (pin "1") (pinfunction "1_1") (pintype "passive"))
      (node (ref "C9") (pin "2") (pinfunction "2_2") (pintype "passive"))
      (node (ref "D10") (pin "2") (pinfunction "VSS_2") (pintype "power_in"))
      (node (ref "D11") (pin "2") (pinfunction "VSS_2") (pintype "power_in"))
      (node (ref "D12") (pin "2") (pinfunction "VSS_2") (pintype "power_in"))
      (node (ref "D13") (pin "2") (pinfunction "VSS_2") (pintype "power_in"))
      (node (ref "D14") (pin "2") (pinfunction "VSS_2") (pintype "power_in"))
      (node (ref "D15") (pin "2") (pinfunction "VSS_2") (pintype "power_in"))
      (node (ref "D16") (pin "2") (pinfunction "VSS_2") (pintype "power_in"))
      (node (ref "D17") (pin "2") (pinfunction "VSS_2") (pintype "power_in"))
      (node (ref "D18") (pin "2") (pinfunction "VSS_2") (pintype "power_in"))
      (node (ref "D19") (pin "2") (pinfunction "VSS_2") (pintype "power_in"))
      (node (ref "D2") (pin "A") (pinfunction "A_A") (pintype "passive"))
      (node (ref "D20") (pin "2") (pinfunction "VSS_2") (pintype "power_in"))
      (node (ref "D21") (pin "2") (pinfunction "VSS_2") (pintype "power_in"))
      (node (ref "D22") (pin "2") (pinfunction "VSS_2") (pintype "power_in"))
      (node (ref "D23") (pin "2") (pinfunction "VSS_2") (pintype "power_in"))
      (node (ref "D4") (pin "A") (pinfunction "A_A") (pintype "passive"))
      (node (ref "D8") (pin "2") (pinfunction "VSS_2") (pintype "power_in"))
      (node (ref "D9") (pin "2") (pinfunction "VSS_2") (pintype "power_in"))
      (node (ref "K1") (pin "0") (pintype "power_in"))
      (node (ref "K1") (pin "2") (pintype "power_in"))
      (node (ref "K1") (pin "3") (pintype "power_in"))
      (node (ref "M1") (pin "1") (pintype "power_in"))
      (node (ref "M2") (pin "1") (pintype "power_in"))
      (node (ref "M3") (pin "1") (pintype "power_in"))
      (node (ref "MOTOR1") (pin "7") (pinfunction "GND_7") (pintype "power_in"))
      (node (ref "MOTOR2") (pin "7") (pinfunction "GND_7") (pintype "power_in"))
      (node (ref "R1") (pin "1") (pinfunction "1_1") (pintype "passive"))
      (node (ref "R12") (pin "1") (pinfunction "1_1") (pintype "passive"))
      (node (ref "R14") (pin "1") (pinfunction "1_1") (pintype "passive"))
      (node (ref "R15") (pin "1") (pinfunction "1_1") (pintype "passive"))
      (node (ref "R16") (pin "1") (pinfunction "1_1") (pintype "passive"))
      (node (ref "R17") (pin "1") (pinfunction "1_1") (pintype "passive"))
      (node (ref "R21") (pin "2") (pinfunction "2_2") (pintype "passive"))
      (node (ref "R22") (pin "1") (pinfunction "1_1") (pintype "passive"))
      (node (ref "R3") (pin "1") (pinfunction "1_1") (pintype "passive"))
      (node (ref "R4") (pin "2") (pinfunction "2_2") (pintype "passive"))
      (node (ref "R7") (pin "1") (pinfunction "1_1") (pintype "passive"))
      (node (ref "R9") (pin "1") (pinfunction "1_1") (pintype "passive"))
      (node (ref "S1") (pin "a1") (pinfunction "a1_a1") (pintype "power_in"))
      (node (ref "S1") (pin "a2") (pinfunction "a2_a2") (pintype "power_in"))
      (node (ref "S1") (pin "b") (pinfunction "b_b") (pintype "power_in"))
      (node (ref "S1") (pin "s1") (pinfunction "s1_s1") (pintype "power_in"))
      (node (ref "S1") (pin "s2") (pinfunction "s2_s2") (pintype "power_in"))
      (node (ref "S2") (pin "2") (pinfunction "NO_2") (pintype "passive"))
      (node (ref "SW1") (pin "1") (pinfunction "1_1") (pintype "power_in"))
      (node (ref "U1") (pin "1") (pinfunction "CLKIN_1") (pintype "power_in"))
      (node (ref "U1") (pin "11") (pinfunction "FSYNC_11") (pintype "power_in"))
      (node (ref "U1") (pin "18") (pinfunction "GND_18") (pintype "power_in"))
      (node (ref "U2") (pin "23") (pinfunction "VSS_23") (pintype "power_in"))
      (node (ref "U2") (pin "35") (pinfunction "VSS_35") (pintype "power_in"))
      (node (ref "U2") (pin "47") (pinfunction "VSS_47") (pintype "power_in"))
      (node (ref "U2") (pin "8") (pinfunction "VSSA_8") (pintype "power_in"))
      (node (ref "U3") (pin "6") (pinfunction "GND_6") (pintype "power_in"))
      (node (ref "U3") (pin "9") (pinfunction "PowerPAD_9") (pintype "power_in"))
      (node (ref "U4") (pin "1") (pinfunction "GND_1") (pintype "power_in"))
      (node (ref "U5") (pin "2") (pinfunction "GND_2") (pintype "power_in"))
      (node (ref "U7") (pin "11") (pinfunction "GND_11") (pintype "power_in"))
      (node (ref "U7") (pin "12") (pinfunction "GND_12") (pintype "power_in"))
      (node (ref "U7") (pin "13") (pinfunction "GND_13") (pintype "power_in"))
      (node (ref "U7") (pin "2") (pinfunction "DIR_2") (pintype "power_in"))
      (node (ref "U7") (pin "22") (pinfunction "~{OE}_22") (pintype "power_in"))
      (node (ref "U8") (pin "1") (pinfunction "NC/GND_1") (pintype "power_in"))
      (node (ref "U8") (pin "10") (pinfunction "BS0_10") (pintype "power_in"))
      (node (ref "U8") (pin "12") (pinfunction "BS2_12") (pintype "power_in"))
      (node (ref "U8") (pin "16") (pinfunction "R/W#_16") (pintype "power_in"))
      (node (ref "U8") (pin "17") (pinfunction "E/RD#_17") (pintype "power_in"))
      (node (ref "U8") (pin "21") (pinfunction "D3_21") (pintype "power_in"))
      (node (ref "U8") (pin "22") (pinfunction "D4_22") (pintype "power_in"))
      (node (ref "U8") (pin "23") (pinfunction "D5_23") (pintype "power_in"))
      (node (ref "U8") (pin "24") (pinfunction "D6_24") (pintype "power_in"))
      (node (ref "U8") (pin "25") (pinfunction "D7_25") (pintype "power_in"))
      (node (ref "U8") (pin "29") (pinfunction "VLSS_29") (pintype "power_in"))
      (node (ref "U8") (pin "30") (pinfunction "NC/GND_30") (pintype "power_in"))
      (node (ref "U8") (pin "8") (pinfunction "VSS_8") (pintype "power_in"))
      (node (ref "U9") (pin "11") (pinfunction "GND_11") (pintype "power_in"))
      (node (ref "U9") (pin "12") (pinfunction "GND_12") (pintype "power_in"))
      (node (ref "U9") (pin "13") (pinfunction "GND_13") (pintype "power_in"))
      (node (ref "U9") (pin "22") (pinfunction "~{OE}_22") (pintype "power_in"))
      (node (ref "UART1") (pin "3") (pinfunction "3_3") (pintype "power_in"))
    )
    (net (code "52") (name "Net-(BAT1-Pad1)") (class "Default")
      (node (ref "BAT1") (pin "1") (pinfunction "1_1") (pintype "power_in"))
      (node (ref "R2") (pin "2") (pinfunction "2_2") (pintype "passive"))
    )
    (net (code "53") (name "Net-(BAT1-Pad2)") (class "Default")
      (node (ref "BAT1") (pin "2") (pinfunction "2_2") (pintype "power_in"))
      (node (ref "R6") (pin "2") (pinfunction "2_2") (pintype "passive"))
    )
    (net (code "54") (name "Net-(BAT1-Pad3)") (class "Default")
      (node (ref "BAT1") (pin "3") (pinfunction "3_3") (pintype "power_in"))
      (node (ref "R8") (pin "2") (pinfunction "2_2") (pintype "passive"))
    )
    (net (code "55") (name "Net-(C17-Pad2)") (class "Default")
      (node (ref "C17") (pin "2") (pinfunction "2_2") (pintype "passive"))
      (node (ref "R19") (pin "1") (pinfunction "1_1") (pintype "passive"))
      (node (ref "R25") (pin "1") (pinfunction "1_1") (pintype "passive"))
      (node (ref "R26") (pin "1") (pinfunction "1_1") (pintype "passive"))
      (node (ref "R27") (pin "1") (pinfunction "1_1") (pintype "passive"))
      (node (ref "R28") (pin "2") (pinfunction "2_2") (pintype "passive"))
    )
    (net (code "56") (name "Net-(D1-K)") (class "Default")
      (node (ref "D1") (pin "2") (pinfunction "K_2") (pintype "passive"))
      (node (ref "R1") (pin "2") (pinfunction "2_2") (pintype "passive"))
    )
    (net (code "57") (name "Net-(D5-K)") (class "Default")
      (node (ref "D5") (pin "2") (pinfunction "K_2") (pintype "passive"))
      (node (ref "R15") (pin "2") (pinfunction "2_2") (pintype "passive"))
    )
    (net (code "58") (name "Net-(D6-K)") (class "Default")
      (node (ref "D6") (pin "2") (pinfunction "K_2") (pintype "passive"))
      (node (ref "R16") (pin "2") (pinfunction "2_2") (pintype "passive"))
    )
    (net (code "59") (name "Net-(D7-K)") (class "Default")
      (node (ref "D7") (pin "2") (pinfunction "K_2") (pintype "passive"))
      (node (ref "R17") (pin "2") (pinfunction "2_2") (pintype "passive"))
    )
    (net (code "60") (name "Net-(D8-DOUT)") (class "Default")
      (node (ref "D8") (pin "1") (pinfunction "DOUT_1") (pintype "power_in"))
      (node (ref "D9") (pin "3") (pinfunction "DIN_3") (pintype "power_in"))
    )
    (net (code "61") (name "Net-(D10-DIN)") (class "Default")
      (node (ref "D10") (pin "3") (pinfunction "DIN_3") (pintype "power_in"))
      (node (ref "D9") (pin "1") (pinfunction "DOUT_1") (pintype "power_in"))
    )
    (net (code "62") (name "Net-(D10-DOUT)") (class "Default")
      (node (ref "D10") (pin "1") (pinfunction "DOUT_1") (pintype "power_in"))
      (node (ref "D11") (pin "3") (pinfunction "DIN_3") (pintype "power_in"))
    )
    (net (code "63") (name "Net-(D11-DOUT)") (class "Default")
      (node (ref "D11") (pin "1") (pinfunction "DOUT_1") (pintype "power_in"))
      (node (ref "D15") (pin "3") (pinfunction "DIN_3") (pintype "power_in"))
    )
    (net (code "64") (name "Net-(D12-DIN)") (class "Default")
      (node (ref "D12") (pin "3") (pinfunction "DIN_3") (pintype "power_in"))
      (node (ref "D13") (pin "1") (pinfunction "DOUT_1") (pintype "power_in"))
    )
    (net (code "65") (name "Net-(D12-DOUT)") (class "Default")
      (node (ref "D12") (pin "1") (pinfunction "DOUT_1") (pintype "power_in"))
      (node (ref "D16") (pin "3") (pinfunction "DIN_3") (pintype "power_in"))
    )
    (net (code "66") (name "Net-(D13-DIN)") (class "Default")
      (node (ref "D13") (pin "3") (pinfunction "DIN_3") (pintype "power_in"))
      (node (ref "D14") (pin "1") (pinfunction "DOUT_1") (pintype "power_in"))
    )
    (net (code "67") (name "Net-(D14-DIN)") (class "Default")
      (node (ref "D14") (pin "3") (pinfunction "DIN_3") (pintype "power_in"))
      (node (ref "D15") (pin "1") (pinfunction "DOUT_1") (pintype "power_in"))
    )
    (net (code "68") (name "Net-(D16-DOUT)") (class "Default")
      (node (ref "D16") (pin "1") (pinfunction "DOUT_1") (pintype "power_in"))
      (node (ref "D17") (pin "3") (pinfunction "DIN_3") (pintype "power_in"))
    )
    (net (code "69") (name "Net-(D17-DOUT)") (class "Default")
      (node (ref "D17") (pin "1") (pinfunction "DOUT_1") (pintype "power_in"))
      (node (ref "D18") (pin "3") (pinfunction "DIN_3") (pintype "power_in"))
    )
    (net (code "70") (name "Net-(D18-DOUT)") (class "Default")
      (node (ref "D18") (pin "1") (pinfunction "DOUT_1") (pintype "power_in"))
      (node (ref "D19") (pin "3") (pinfunction "DIN_3") (pintype "power_in"))
    )
    (net (code "71") (name "Net-(D19-DOUT)") (class "Default")
      (node (ref "D19") (pin "1") (pinfunction "DOUT_1") (pintype "power_in"))
      (node (ref "D23") (pin "3") (pinfunction "DIN_3") (pintype "power_in"))
    )
    (net (code "72") (name "Net-(D20-DIN)") (class "Default")
      (node (ref "D20") (pin "3") (pinfunction "DIN_3") (pintype "power_in"))
      (node (ref "D21") (pin "1") (pinfunction "DOUT_1") (pintype "power_in"))
    )
    (net (code "73") (name "Net-(D21-DIN)") (class "Default")
      (node (ref "D21") (pin "3") (pinfunction "DIN_3") (pintype "power_in"))
      (node (ref "D22") (pin "1") (pinfunction "DOUT_1") (pintype "power_in"))
    )
    (net (code "74") (name "Net-(D22-DIN)") (class "Default")
      (node (ref "D22") (pin "3") (pinfunction "DIN_3") (pintype "power_in"))
      (node (ref "D23") (pin "1") (pinfunction "DOUT_1") (pintype "power_in"))
    )
    (net (code "75") (name "Net-(FB4-Pad1)") (class "Default")
      (node (ref "FB4") (pin "1") (pinfunction "1_1") (pintype "passive"))
      (node (ref "U7") (pin "23") (pinfunction "VCCB_23") (pintype "power_in"))
      (node (ref "U7") (pin "24") (pinfunction "VCCB_24") (pintype "power_in"))
    )
    (net (code "76") (name "Net-(FB6-Pad1)") (class "Default")
      (node (ref "FB6") (pin "1") (pinfunction "1_1") (pintype "passive"))
      (node (ref "U9") (pin "23") (pinfunction "VCCB_23") (pintype "power_in"))
      (node (ref "U9") (pin "24") (pinfunction "VCCB_24") (pintype "power_in"))
    )
    (net (code "77") (name "Net-(J1--)") (class "Default")
      (node (ref "J1") (pin "2") (pinfunction "-_2") (pintype "power_in"))
      (node (ref "K1") (pin "1") (pintype "power_in"))
    )
    (net (code "78") (name "Net-(R25-Pad2)") (class "Default")
      (node (ref "R25") (pin "2") (pinfunction "2_2") (pintype "passive"))
      (node (ref "S1") (pin "f") (pinfunction "f_f") (pintype "power_in"))
      (node (ref "S1") (pin "g") (pinfunction "g_g") (pintype "power_in"))
    )
    (net (code "79") (name "Net-(R26-Pad2)") (class "Default")
      (node (ref "R26") (pin "2") (pinfunction "2_2") (pintype "passive"))
      (node (ref "S1") (pin "e") (pinfunction "e_e") (pintype "power_in"))
    )
    (net (code "80") (name "Net-(R27-Pad2)") (class "Default")
      (node (ref "R27") (pin "2") (pinfunction "2_2") (pintype "passive"))
      (node (ref "S1") (pin "c") (pinfunction "c_c") (pintype "power_in"))
      (node (ref "S1") (pin "d") (pinfunction "d_d") (pintype "power_in"))
    )
    (net (code "81") (name "Net-(U1-AD0)") (class "Default")
      (node (ref "R12") (pin "2") (pinfunction "2_2") (pintype "passive"))
      (node (ref "U1") (pin "9") (pinfunction "AD0_9") (pintype "power_in"))
    )
    (net (code "82") (name "Net-(U1-CPOUT)") (class "Default")
      (node (ref "C2") (pin "1") (pinfunction "1_1") (pintype "passive"))
      (node (ref "U1") (pin "20") (pinfunction "CPOUT_20") (pintype "power_in"))
    )
    (net (code "83") (name "Net-(U1-REGOUT)") (class "Default")
      (node (ref "C8") (pin "2") (pinfunction "2_2") (pintype "passive"))
      (node (ref "U1") (pin "10") (pinfunction "REGOUT_10") (pintype "power_in"))
    )
    (net (code "84") (name "Net-(U2-BOOT)") (class "Default")
      (node (ref "R4") (pin "1") (pinfunction "1_1") (pintype "passive"))
      (node (ref "U2") (pin "44") (pinfunction "BOOT_44") (pintype "tri_state"))
    )
    (net (code "85") (name "Net-(U2-VCAP1)") (class "Default")
      (node (ref "C11") (pin "1") (pinfunction "1_1") (pintype "passive"))
      (node (ref "U2") (pin "22") (pinfunction "VCAP1_22") (pintype "power_in"))
    )
    (net (code "86") (name "Net-(U2-VREF+)") (class "Default")
      (node (ref "FB1") (pin "2") (pinfunction "2_2") (pintype "passive"))
      (node (ref "U2") (pin "9") (pinfunction "VREF+_9") (pintype "power_in"))
    )
    (net (code "87") (name "Net-(U3-BOOT)") (class "Default")
      (node (ref "C6") (pin "2") (pinfunction "2_2") (pintype "passive"))
      (node (ref "U3") (pin "1") (pinfunction "BOOT_1") (pintype "power_in"))
    )
    (net (code "88") (name "Net-(U3-PH)") (class "Default")
      (node (ref "C6") (pin "1") (pinfunction "1_1") (pintype "passive"))
      (node (ref "D4") (pin "K") (pinfunction "K_K") (pintype "passive"))
      (node (ref "L1") (pin "1") (pinfunction "1_1") (pintype "passive"))
      (node (ref "U3") (pin "8") (pinfunction "PH_8") (pintype "power_in"))
    )
    (net (code "89") (name "Net-(U3-VSENSE)") (class "Default")
      (node (ref "R13") (pin "1") (pinfunction "1_1") (pintype "passive"))
      (node (ref "R14") (pin "2") (pinfunction "2_2") (pintype "passive"))
      (node (ref "U3") (pin "4") (pinfunction "VSENSE_4") (pintype "power_in"))
    )
    (net (code "90") (name "Net-(U4-OUT)") (class "Default")
      (node (ref "C22") (pin "1") (pinfunction "1_1") (pintype "passive"))
      (node (ref "C23") (pin "1") (pinfunction "1_1") (pintype "passive"))
      (node (ref "FB2") (pin "1") (pinfunction "1_1") (pintype "passive"))
      (node (ref "U4") (pin "2") (pinfunction "OUT_2") (pintype "power_in"))
      (node (ref "U4") (pin "4") (pinfunction "TAB_4") (pintype "power_in"))
    )
    (net (code "91") (name "Net-(U7-VCCA)") (class "Default")
      (node (ref "C30") (pin "2") (pinfunction "2_2") (pintype "passive"))
      (node (ref "FB3") (pin "1") (pinfunction "1_1") (pintype "passive"))
      (node (ref "U7") (pin "1") (pinfunction "VCCA_1") (pintype "power_in"))
    )
    (net (code "92") (name "Net-(U8-C1N)") (class "Default")
      (node (ref "C37") (pin "2") (pinfunction "2_2") (pintype "passive"))
      (node (ref "U8") (pin "5") (pinfunction "C1N_5") (pintype "power_in"))
    )
    (net (code "93") (name "Net-(U8-C1P)") (class "Default")
      (node (ref "C37") (pin "1") (pinfunction "1_1") (pintype "passive"))
      (node (ref "U8") (pin "4") (pinfunction "C1P_4") (pintype "power_in"))
    )
    (net (code "94") (name "Net-(U8-C2N)") (class "Default")
      (node (ref "C36") (pin "2") (pinfunction "2_2") (pintype "passive"))
      (node (ref "U8") (pin "3") (pinfunction "C2N_3") (pintype "power_in"))
    )
    (net (code "95") (name "Net-(U8-C2P)") (class "Default")
      (node (ref "C36") (pin "1") (pinfunction "1_1") (pintype "passive"))
      (node (ref "U8") (pin "2") (pinfunction "C2P_2") (pintype "power_in"))
    )
    (net (code "96") (name "Net-(U8-D{slash}C#)") (class "Default")
      (node (ref "R22") (pin "2") (pinfunction "2_2") (pintype "passive"))
      (node (ref "U8") (pin "15") (pinfunction "D/C#_15") (pintype "power_in"))
    )
    (net (code "97") (name "Net-(U8-IREF)") (class "Default")
      (node (ref "R21") (pin "1") (pinfunction "1_1") (pintype "passive"))
      (node (ref "U8") (pin "26") (pinfunction "IREF_26") (pintype "power_in"))
    )
    (net (code "98") (name "Net-(U8-VCC)") (class "Default")
      (node (ref "C38") (pin "1") (pinfunction "1_1") (pintype "passive"))
      (node (ref "U8") (pin "28") (pinfunction "VCC_28") (pintype "power_in"))
    )
    (net (code "99") (name "Net-(U8-VCOMH)") (class "Default")
      (node (ref "C35") (pin "1") (pinfunction "1_1") (pintype "passive"))
      (node (ref "U8") (pin "27") (pinfunction "VCOMH_27") (pintype "power_in"))
    )
    (net (code "100") (name "Net-(U9-DIR)") (class "Default")
      (node (ref "C32") (pin "2") (pinfunction "2_2") (pintype "passive"))
      (node (ref "FB5") (pin "1") (pinfunction "1_1") (pintype "passive"))
      (node (ref "U9") (pin "1") (pinfunction "VCCA_1") (pintype "power_in"))
      (node (ref "U9") (pin "2") (pinfunction "DIR_2") (pintype "power_in"))
    )
    (net (code "101") (name "unconnected-(C1-CC1-PadA5)") (class "Default")
      (node (ref "C1") (pin "A5") (pinfunction "CC1_A5") (pintype "bidirectional+no_connect"))
    )
    (net (code "102") (name "unconnected-(C1-CC2-PadB5)") (class "Default")
      (node (ref "C1") (pin "B5") (pinfunction "CC2_B5") (pintype "bidirectional+no_connect"))
    )
    (net (code "103") (name "unconnected-(C1-SBU1-PadA8)") (class "Default")
      (node (ref "C1") (pin "A8") (pinfunction "SBU1_A8") (pintype "bidirectional+no_connect"))
    )
    (net (code "104") (name "unconnected-(C1-SBU2-PadB8)") (class "Default")
      (node (ref "C1") (pin "B8") (pinfunction "SBU2_B8") (pintype "bidirectional+no_connect"))
    )
    (net (code "105") (name "unconnected-(D20-DOUT-Pad1)") (class "Default")
      (node (ref "D20") (pin "1") (pinfunction "DOUT_1") (pintype "power_in"))
    )
    (net (code "106") (name "unconnected-(M14-Pad1)") (class "Default")
      (node (ref "M14") (pin "1") (pinfunction "1_1") (pintype "power_in+no_connect"))
    )
    (net (code "107") (name "unconnected-(M15-Pad1)") (class "Default")
      (node (ref "M15") (pin "1") (pinfunction "1_1") (pintype "power_in+no_connect"))
    )
    (net (code "108") (name "unconnected-(M16-Pad1)") (class "Default")
      (node (ref "M16") (pin "1") (pinfunction "1_1") (pintype "power_in+no_connect"))
    )
    (net (code "109") (name "unconnected-(M17-Pad1)") (class "Default")
      (node (ref "M17") (pin "1") (pinfunction "1_1") (pintype "power_in+no_connect"))
    )
    (net (code "110") (name "unconnected-(M18-Pad1)") (class "Default")
      (node (ref "M18") (pin "1") (pinfunction "1_1") (pintype "power_in+no_connect"))
    )
    (net (code "111") (name "unconnected-(M19-Pad1)") (class "Default")
      (node (ref "M19") (pin "1") (pinfunction "1_1") (pintype "power_in+no_connect"))
    )
    (net (code "112") (name "unconnected-(U1-CL-Pad7)") (class "Default")
      (node (ref "U1") (pin "7") (pinfunction "CL_7") (pintype "power_in+no_connect"))
    )
    (net (code "113") (name "unconnected-(U1-CLKOUT-Pad22)") (class "Default")
      (node (ref "U1") (pin "22") (pinfunction "CLKOUT_22") (pintype "power_in+no_connect"))
    )
    (net (code "114") (name "unconnected-(U1-DA-Pad6)") (class "Default")
      (node (ref "U1") (pin "6") (pinfunction "DA_6") (pintype "power_in+no_connect"))
    )
    (net (code "115") (name "unconnected-(U1-NC-Pad2)") (class "Default")
      (node (ref "U1") (pin "2") (pinfunction "NC_2") (pintype "power_in+no_connect"))
    )
    (net (code "116") (name "unconnected-(U1-NC-Pad3)") (class "Default")
      (node (ref "U1") (pin "3") (pinfunction "NC_3") (pintype "power_in+no_connect"))
    )
    (net (code "117") (name "unconnected-(U1-NC-Pad4)") (class "Default")
      (node (ref "U1") (pin "4") (pinfunction "NC_4") (pintype "power_in+no_connect"))
    )
    (net (code "118") (name "unconnected-(U1-NC-Pad5)") (class "Default")
      (node (ref "U1") (pin "5") (pinfunction "NC_5") (pintype "power_in+no_connect"))
    )
    (net (code "119") (name "unconnected-(U1-NC-Pad14)") (class "Default")
      (node (ref "U1") (pin "14") (pinfunction "NC_14") (pintype "power_in+no_connect"))
    )
    (net (code "120") (name "unconnected-(U1-NC-Pad15)") (class "Default")
      (node (ref "U1") (pin "15") (pinfunction "NC_15") (pintype "power_in+no_connect"))
    )
    (net (code "121") (name "unconnected-(U1-NC-Pad16)") (class "Default")
      (node (ref "U1") (pin "16") (pinfunction "NC_16") (pintype "power_in+no_connect"))
    )
    (net (code "122") (name "unconnected-(U1-NC-Pad17)") (class "Default")
      (node (ref "U1") (pin "17") (pinfunction "NC_17") (pintype "power_in+no_connect"))
    )
    (net (code "123") (name "unconnected-(U1-P-Pad25)") (class "Default")
      (node (ref "U1") (pin "25") (pinfunction "P_25") (pintype "power_in+no_connect"))
    )
    (net (code "124") (name "unconnected-(U1-RESV-Pad19)") (class "Default")
      (node (ref "U1") (pin "19") (pinfunction "RESV_19") (pintype "power_in+no_connect"))
    )
    (net (code "125") (name "unconnected-(U1-RESV-Pad21)") (class "Default")
      (node (ref "U1") (pin "21") (pinfunction "RESV_21") (pintype "power_in+no_connect"))
    )
    (net (code "126") (name "unconnected-(U2-PA5-Pad15)") (class "Default")
      (node (ref "U2") (pin "15") (pinfunction "PA5_15") (pintype "bidirectional+no_connect"))
    )
    (net (code "127") (name "unconnected-(U2-PA15-Pad38)") (class "Default")
      (node (ref "U2") (pin "38") (pinfunction "PA15_38") (pintype "bidirectional+no_connect"))
    )
    (net (code "128") (name "unconnected-(U2-PB4-Pad40)") (class "Default")
      (node (ref "U2") (pin "40") (pinfunction "PB4_40") (pintype "bidirectional+no_connect"))
    )
    (net (code "129") (name "unconnected-(U3-ENA-Pad5)") (class "Default")
      (node (ref "U3") (pin "5") (pinfunction "ENA_5") (pintype "power_in+no_connect"))
    )
    (net (code "130") (name "unconnected-(U3-NC-Pad2)") (class "Default")
      (node (ref "U3") (pin "2") (pinfunction "NC_2") (pintype "power_in+no_connect"))
    )
    (net (code "131") (name "unconnected-(U3-NC-Pad3)") (class "Default")
      (node (ref "U3") (pin "3") (pinfunction "NC_3") (pintype "power_in+no_connect"))
    )
    (net (code "132") (name "unconnected-(U7-A1-Pad3)") (class "Default")
      (node (ref "U7") (pin "3") (pinfunction "A1_3") (pintype "power_in"))
    )
    (net (code "133") (name "unconnected-(U7-A2-Pad4)") (class "Default")
      (node (ref "U7") (pin "4") (pinfunction "A2_4") (pintype "power_in"))
    )
    (net (code "134") (name "unconnected-(U7-B1-Pad21)") (class "Default")
      (node (ref "U7") (pin "21") (pinfunction "B1_21") (pintype "power_in"))
    )
    (net (code "135") (name "unconnected-(U7-B2-Pad20)") (class "Default")
      (node (ref "U7") (pin "20") (pinfunction "B2_20") (pintype "power_in"))
    )
    (net (code "136") (name "unconnected-(U8-CS#-Pad13)") (class "Default")
      (node (ref "U8") (pin "13") (pinfunction "CS#_13") (pintype "power_in+no_connect"))
    )
    (net (code "137") (name "unconnected-(U8-N.C.-Pad7)") (class "Default")
      (node (ref "U8") (pin "7") (pinfunction "N.C._7") (pintype "power_in+no_connect"))
    )
    (net (code "138") (name "unconnected-(U9-A1-Pad3)") (class "Default")
      (node (ref "U9") (pin "3") (pinfunction "A1_3") (pintype "power_in"))
    )
    (net (code "139") (name "unconnected-(U9-A2-Pad4)") (class "Default")
      (node (ref "U9") (pin "4") (pinfunction "A2_4") (pintype "power_in"))
    )
    (net (code "140") (name "unconnected-(U9-A3-Pad5)") (class "Default")
      (node (ref "U9") (pin "5") (pinfunction "A3_5") (pintype "power_in"))
    )
    (net (code "141") (name "unconnected-(U9-A4-Pad6)") (class "Default")
      (node (ref "U9") (pin "6") (pinfunction "A4_6") (pintype "power_in"))
    )
    (net (code "142") (name "unconnected-(U9-B1-Pad21)") (class "Default")
      (node (ref "U9") (pin "21") (pinfunction "B1_21") (pintype "power_in"))
    )
    (net (code "143") (name "unconnected-(U9-B2-Pad20)") (class "Default")
      (node (ref "U9") (pin "20") (pinfunction "B2_20") (pintype "power_in"))
    )
    (net (code "144") (name "unconnected-(U9-B3-Pad19)") (class "Default")
      (node (ref "U9") (pin "19") (pinfunction "B3_19") (pintype "power_in"))
    )
    (net (code "145") (name "unconnected-(U9-B4-Pad18)") (class "Default")
      (node (ref "U9") (pin "18") (pinfunction "B4_18") (pintype "power_in"))
    )
  )
)
